# V2.net
KiCad netlist of a schematic drawn in EAGLE
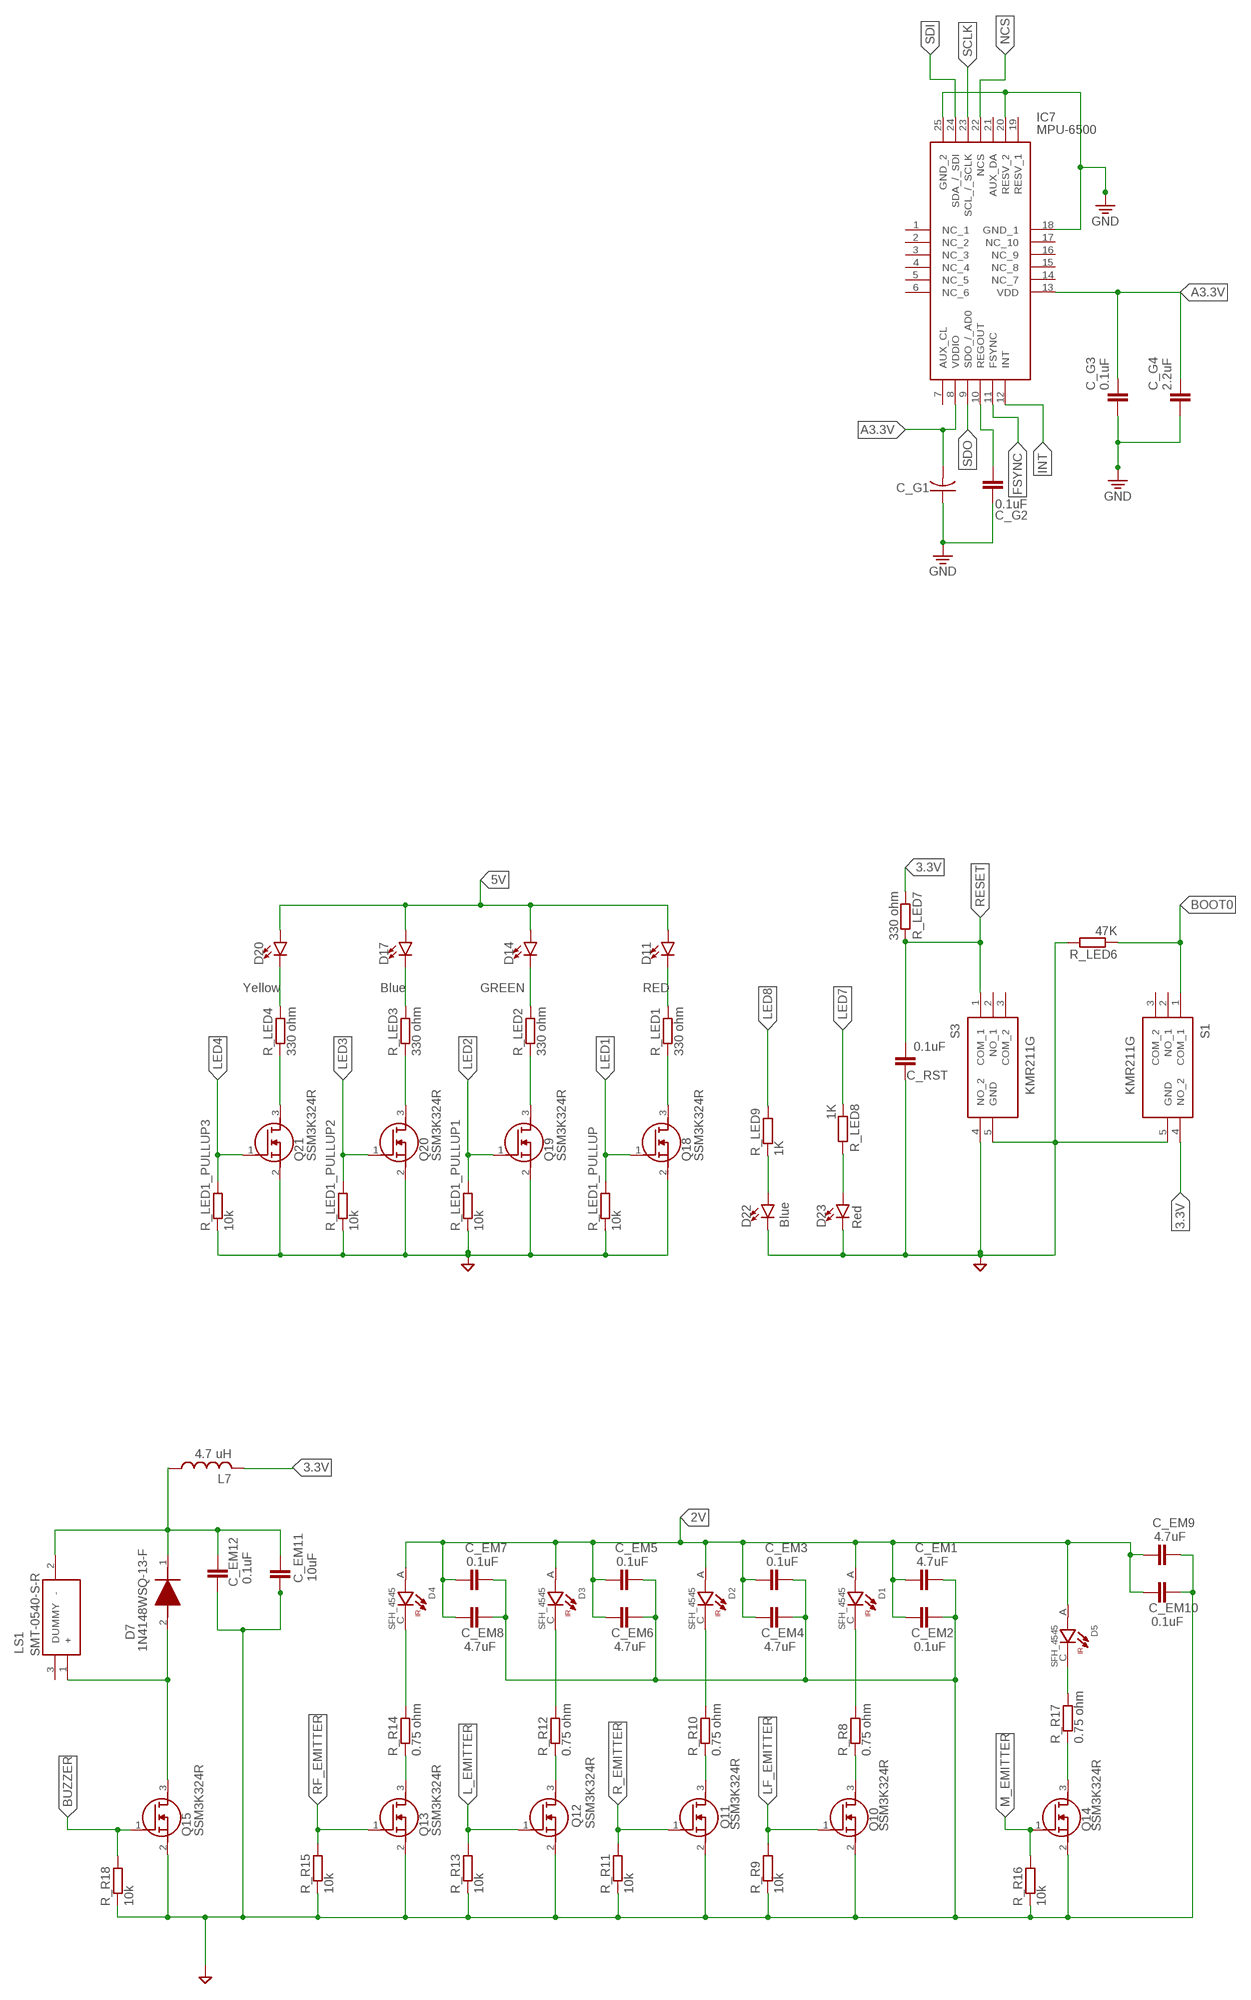
[diagram p0: schematic, sheet 1, part 1 of 2]
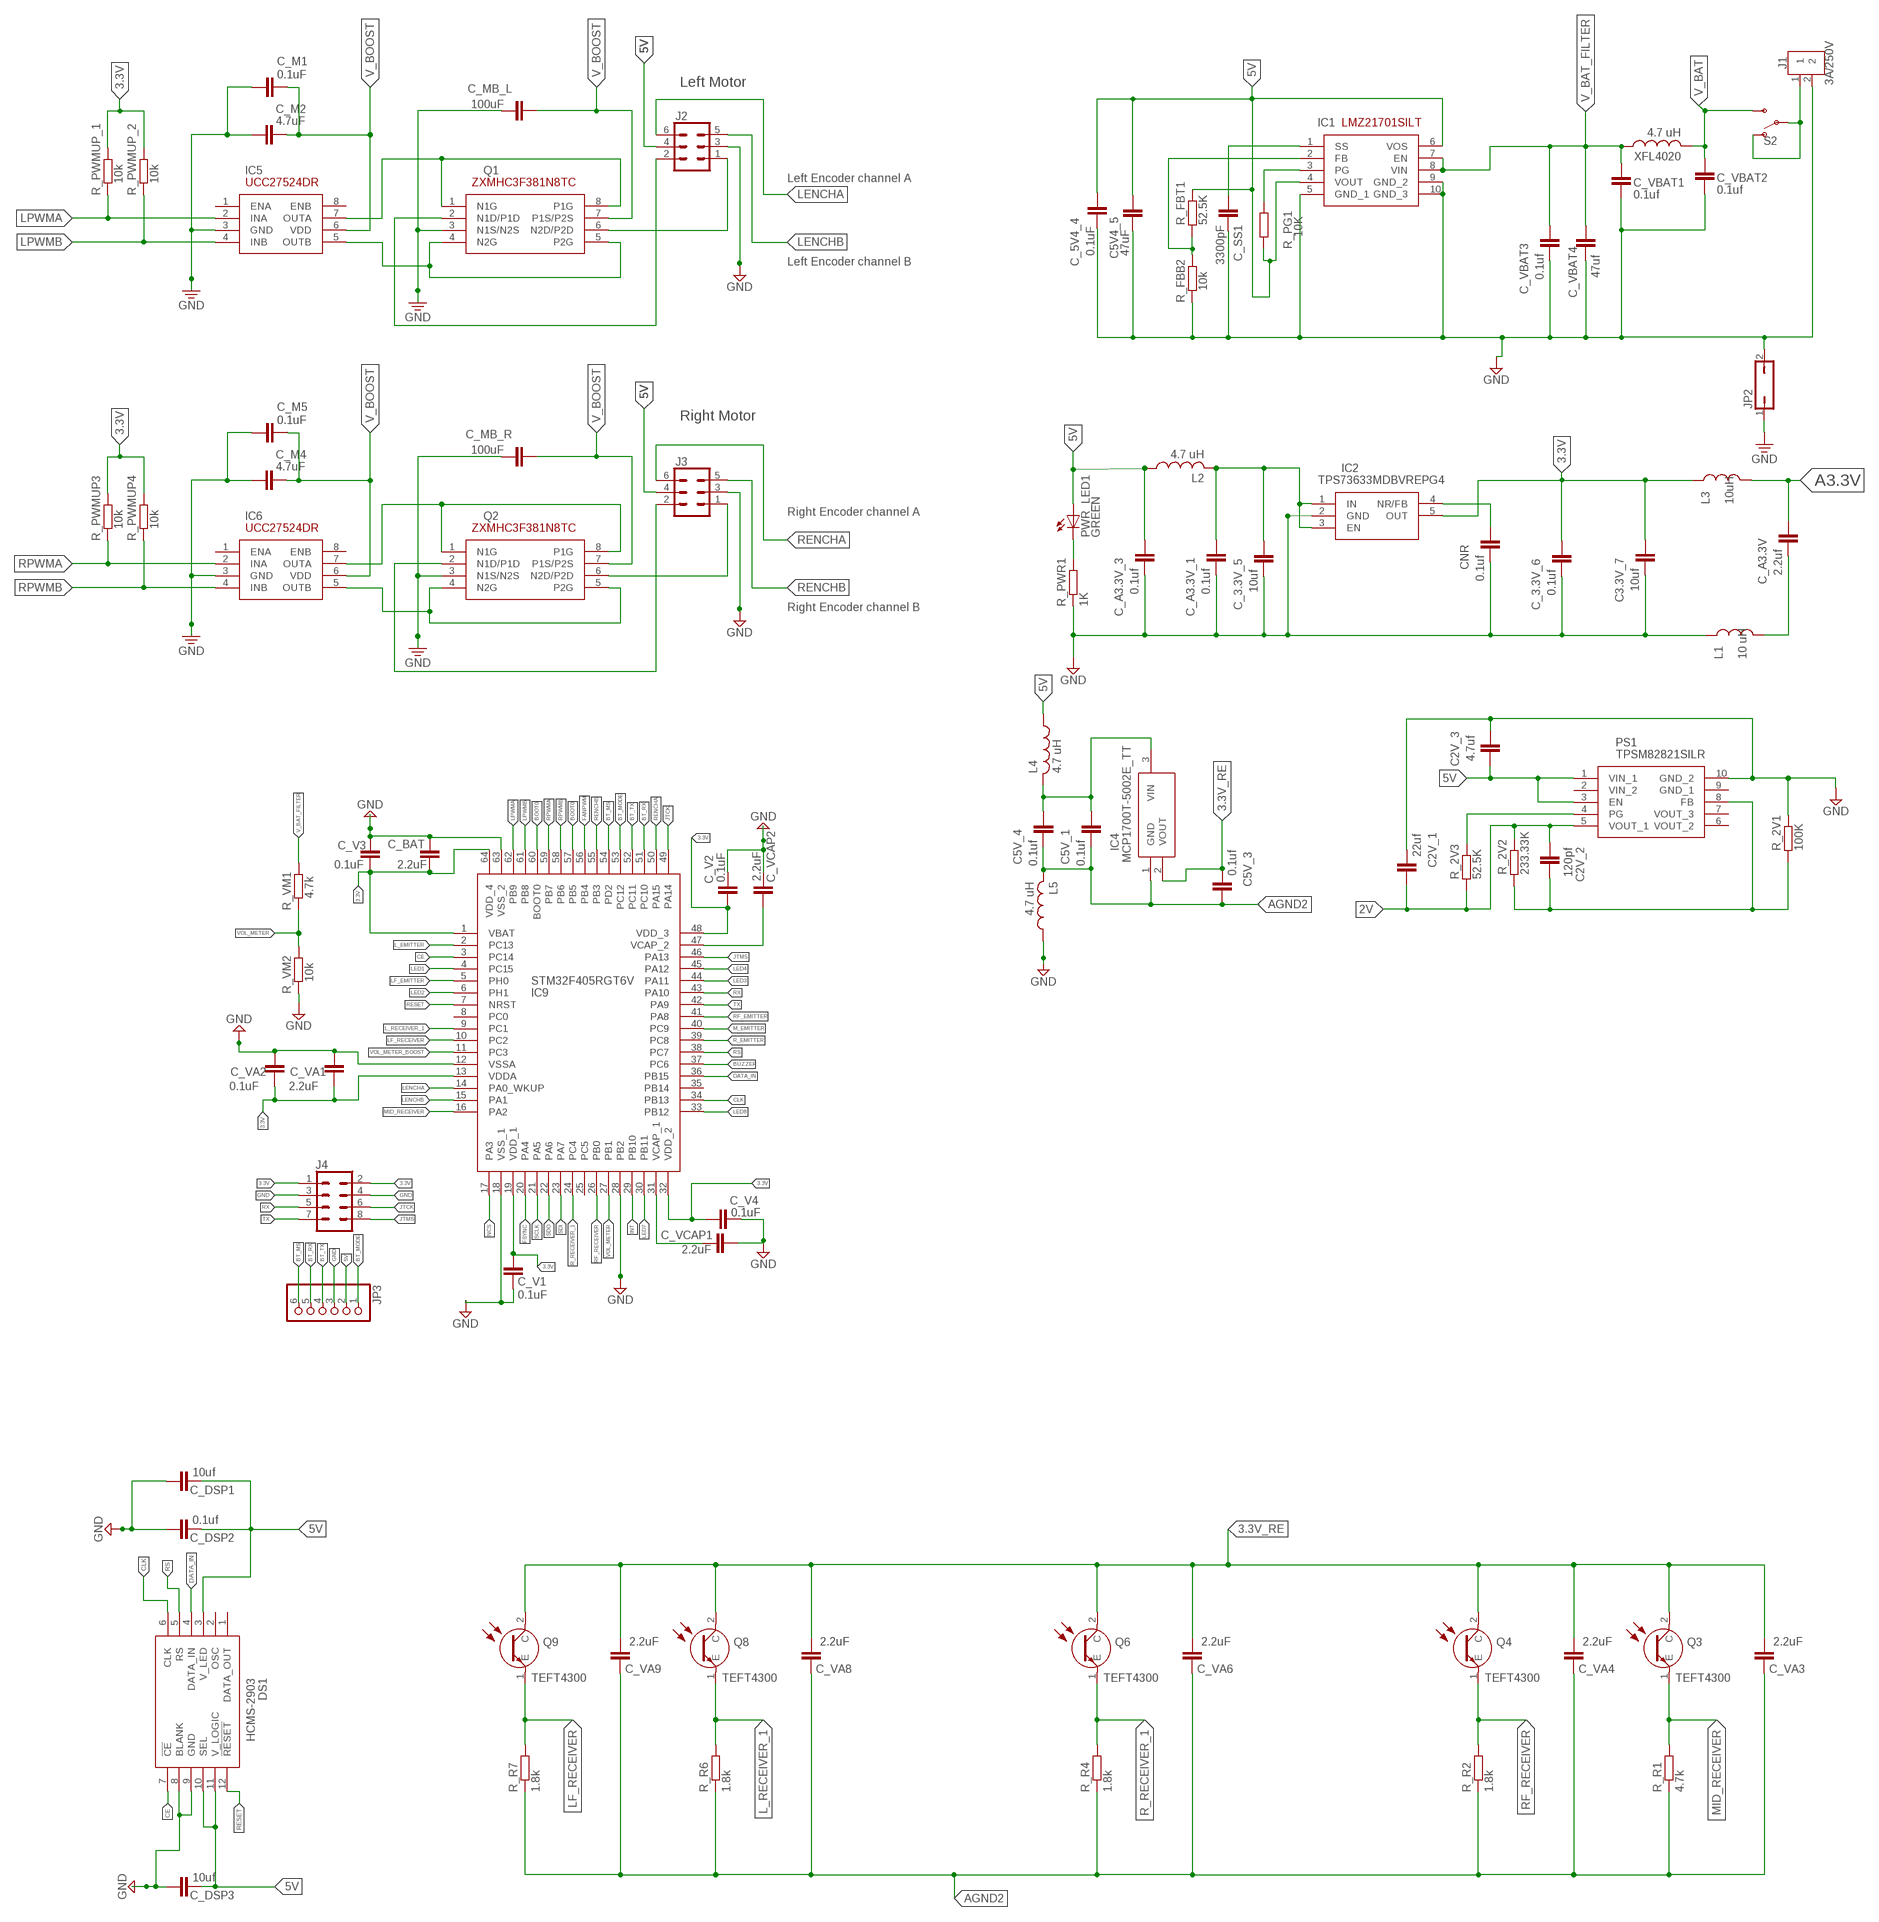
[diagram p1: schematic, sheet 1, part 2 of 2]

(export (version "E")
  (design (tool "Eeschema 10.0.6"))
  (components
    (comp (ref "C2V_1")
      (value "22uf")
      (footprint "eagle-import:CAPC2012X110")
      (libsource (lib "eagle-import") (part "CCHIP-0805(2012-METRIC)_"))
    )
    (comp (ref "C2V_2")
      (value "120pf")
      (footprint "eagle-import:CAPC2012X110")
      (libsource (lib "eagle-import") (part "CCHIP-0805(2012-METRIC)_"))
    )
    (comp (ref "C2V_3")
      (value "4.7uf")
      (footprint "eagle-import:CAPC2012X110")
      (libsource (lib "eagle-import") (part "CCHIP-0805(2012-METRIC)_"))
    )
    (comp (ref "C3.3V_7")
      (value "10uf")
      (footprint "eagle-import:CAPC2012X110")
      (libsource (lib "eagle-import") (part "CCHIP-0805(2012-METRIC)_"))
    )
    (comp (ref "C5V4_5")
      (value "47uF")
      (footprint "eagle-import:CAPC2012X110")
      (libsource (lib "eagle-import") (part "CCHIP-0805(2012-METRIC)_"))
    )
    (comp (ref "C5V_1")
      (value "0.1uf")
      (footprint "eagle-import:CAPC2012X110")
      (libsource (lib "eagle-import") (part "CCHIP-0805(2012-METRIC)_"))
    )
    (comp (ref "C5V_3")
      (value "0.1uf")
      (footprint "eagle-import:CAPC2012X110")
      (libsource (lib "eagle-import") (part "CCHIP-0805(2012-METRIC)_"))
    )
    (comp (ref "C5V_4")
      (value "0.1uf")
      (footprint "eagle-import:CAPC2012X110")
      (libsource (lib "eagle-import") (part "CCHIP-0805(2012-METRIC)_"))
    )
    (comp (ref "CNR")
      (value "0.1uf")
      (footprint "eagle-import:CAPC2012X110")
      (libsource (lib "eagle-import") (part "CCHIP-0805(2012-METRIC)_"))
    )
    (comp (ref "C_3.3V_5")
      (value "10uf")
      (footprint "eagle-import:CAPC2012X110")
      (libsource (lib "eagle-import") (part "CCHIP-0805(2012-METRIC)_"))
    )
    (comp (ref "C_3.3V_6")
      (value "0.1uf")
      (footprint "eagle-import:CAPC2012X110")
      (libsource (lib "eagle-import") (part "CCHIP-0805(2012-METRIC)_"))
    )
    (comp (ref "C_5V4_4")
      (value "0.1uF")
      (footprint "eagle-import:CAPC2012X110")
      (libsource (lib "eagle-import") (part "CCHIP-0805(2012-METRIC)_"))
    )
    (comp (ref "C_A3.3V")
      (value "2.2uf")
      (footprint "eagle-import:CAPC2012X110")
      (libsource (lib "eagle-import") (part "CCHIP-0805(2012-METRIC)_"))
    )
    (comp (ref "C_A3.3V_1")
      (value "0.1uf")
      (footprint "eagle-import:CAPC2012X110")
      (libsource (lib "eagle-import") (part "CCHIP-0805(2012-METRIC)_"))
    )
    (comp (ref "C_A3.3V_3")
      (value "0.1uf")
      (footprint "eagle-import:CAPC2012X110")
      (libsource (lib "eagle-import") (part "CCHIP-0805(2012-METRIC)_"))
    )
    (comp (ref "C_BAT")
      (value "2.2uF")
      (footprint "eagle-import:CAPC2012X110")
      (libsource (lib "eagle-import") (part "CCHIP-0805(2012-METRIC)_"))
    )
    (comp (ref "C_DSP1")
      (value "10uf")
      (footprint "eagle-import:CAPC2012X110")
      (libsource (lib "eagle-import") (part "CCHIP-0805(2012-METRIC)_"))
    )
    (comp (ref "C_DSP2")
      (value "0.1uf")
      (footprint "eagle-import:CAPC2012X110")
      (libsource (lib "eagle-import") (part "CCHIP-0805(2012-METRIC)_"))
    )
    (comp (ref "C_DSP3")
      (value "10uf")
      (footprint "eagle-import:CAPC2012X110")
      (libsource (lib "eagle-import") (part "CCHIP-0805(2012-METRIC)_"))
    )
    (comp (ref "C_EM1")
      (value "4.7uF")
      (footprint "eagle-import:CAPC2012X110")
      (libsource (lib "eagle-import") (part "CCHIP-0805(2012-METRIC)_"))
    )
    (comp (ref "C_EM2")
      (value "0.1uF")
      (footprint "eagle-import:CAPC2012X110")
      (libsource (lib "eagle-import") (part "CCHIP-0805(2012-METRIC)_"))
    )
    (comp (ref "C_EM3")
      (value "0.1uF")
      (footprint "eagle-import:CAPC2012X110")
      (libsource (lib "eagle-import") (part "CCHIP-0805(2012-METRIC)_"))
    )
    (comp (ref "C_EM4")
      (value "4.7uF")
      (footprint "eagle-import:CAPC2012X110")
      (libsource (lib "eagle-import") (part "CCHIP-0805(2012-METRIC)_"))
    )
    (comp (ref "C_EM5")
      (value "0.1uF")
      (footprint "eagle-import:CAPC2012X110")
      (libsource (lib "eagle-import") (part "CCHIP-0805(2012-METRIC)_"))
    )
    (comp (ref "C_EM6")
      (value "4.7uF")
      (footprint "eagle-import:CAPC2012X110")
      (libsource (lib "eagle-import") (part "CCHIP-0805(2012-METRIC)_"))
    )
    (comp (ref "C_EM7")
      (value "0.1uF")
      (footprint "eagle-import:CAPC2012X110")
      (libsource (lib "eagle-import") (part "CCHIP-0805(2012-METRIC)_"))
    )
    (comp (ref "C_EM8")
      (value "4.7uF")
      (footprint "eagle-import:CAPC2012X110")
      (libsource (lib "eagle-import") (part "CCHIP-0805(2012-METRIC)_"))
    )
    (comp (ref "C_EM9")
      (value "4.7uF")
      (footprint "eagle-import:CAPC2012X110")
      (libsource (lib "eagle-import") (part "CCHIP-0805(2012-METRIC)_"))
    )
    (comp (ref "C_EM10")
      (value "0.1uF")
      (footprint "eagle-import:CAPC2012X110")
      (libsource (lib "eagle-import") (part "CCHIP-0805(2012-METRIC)_"))
    )
    (comp (ref "C_EM11")
      (value "10uF")
      (footprint "eagle-import:CAPC2012X110")
      (libsource (lib "eagle-import") (part "CCHIP-0805(2012-METRIC)_"))
    )
    (comp (ref "C_EM12")
      (value "0.1uF")
      (footprint "eagle-import:CAPC2012X110")
      (libsource (lib "eagle-import") (part "CCHIP-0805(2012-METRIC)_"))
    )
    (comp (ref "C_G1")
      (value "0.01uF")
      (footprint "eagle-import:C0603K")
      (libsource (lib "eagle-import") (part "C-USC0603K"))
    )
    (comp (ref "C_G2")
      (value "0.1uF")
      (footprint "eagle-import:CAPC2012X110")
      (libsource (lib "eagle-import") (part "CCHIP-0805(2012-METRIC)_"))
    )
    (comp (ref "C_G3")
      (value "0.1uF")
      (footprint "eagle-import:CAPC2012X110")
      (libsource (lib "eagle-import") (part "CCHIP-0805(2012-METRIC)_"))
    )
    (comp (ref "C_G4")
      (value "2.2uF")
      (footprint "eagle-import:CAPC2012X110")
      (libsource (lib "eagle-import") (part "CCHIP-0805(2012-METRIC)_"))
    )
    (comp (ref "C_M1")
      (value "0.1uF")
      (footprint "eagle-import:CAPC2012X110")
      (libsource (lib "eagle-import") (part "CCHIP-0805(2012-METRIC)_"))
    )
    (comp (ref "C_M2")
      (value "4.7uF")
      (footprint "eagle-import:CAPC2012X110")
      (libsource (lib "eagle-import") (part "CCHIP-0805(2012-METRIC)_"))
    )
    (comp (ref "C_M4")
      (value "4.7uF")
      (footprint "eagle-import:CAPC2012X110")
      (libsource (lib "eagle-import") (part "CCHIP-0805(2012-METRIC)_"))
    )
    (comp (ref "C_M5")
      (value "0.1uF")
      (footprint "eagle-import:CAPC2012X110")
      (libsource (lib "eagle-import") (part "CCHIP-0805(2012-METRIC)_"))
    )
    (comp (ref "C_MB_L")
      (value "100uF")
      (footprint "eagle-import:CAPC2012X110")
      (libsource (lib "eagle-import") (part "CCHIP-0805(2012-METRIC)_"))
    )
    (comp (ref "C_MB_R")
      (value "100uF")
      (footprint "eagle-import:CAPC2012X110")
      (libsource (lib "eagle-import") (part "CCHIP-0805(2012-METRIC)_"))
    )
    (comp (ref "C_RST")
      (value "0.1uF")
      (footprint "eagle-import:CAPC2012X110")
      (libsource (lib "eagle-import") (part "CCHIP-0805(2012-METRIC)_"))
    )
    (comp (ref "C_SS1")
      (value "3300pF")
      (footprint "eagle-import:CAPC2012X110")
      (libsource (lib "eagle-import") (part "CCHIP-0805(2012-METRIC)_"))
    )
    (comp (ref "C_V1")
      (value "0.1uF")
      (footprint "eagle-import:CAPC2012X110")
      (libsource (lib "eagle-import") (part "CCHIP-0805(2012-METRIC)_"))
    )
    (comp (ref "C_V2")
      (value "0.1uF")
      (footprint "eagle-import:CAPC2012X110")
      (libsource (lib "eagle-import") (part "CCHIP-0805(2012-METRIC)_"))
    )
    (comp (ref "C_V3")
      (value "0.1uF")
      (footprint "eagle-import:CAPC2012X110")
      (libsource (lib "eagle-import") (part "CCHIP-0805(2012-METRIC)_"))
    )
    (comp (ref "C_V4")
      (value "0.1uF")
      (footprint "eagle-import:CAPC2012X110")
      (libsource (lib "eagle-import") (part "CCHIP-0805(2012-METRIC)_"))
    )
    (comp (ref "C_VA1")
      (value "2.2uF")
      (footprint "eagle-import:CAPC2012X110")
      (libsource (lib "eagle-import") (part "CCHIP-0805(2012-METRIC)_"))
    )
    (comp (ref "C_VA2")
      (value "0.1uF")
      (footprint "eagle-import:CAPC2012X110")
      (libsource (lib "eagle-import") (part "CCHIP-0805(2012-METRIC)_"))
    )
    (comp (ref "C_VA3")
      (value "2.2uF")
      (footprint "eagle-import:CAPC2012X110")
      (libsource (lib "eagle-import") (part "CCHIP-0805(2012-METRIC)_"))
    )
    (comp (ref "C_VA4")
      (value "2.2uF")
      (footprint "eagle-import:CAPC2012X110")
      (libsource (lib "eagle-import") (part "CCHIP-0805(2012-METRIC)_"))
    )
    (comp (ref "C_VA6")
      (value "2.2uF")
      (footprint "eagle-import:CAPC2012X110")
      (libsource (lib "eagle-import") (part "CCHIP-0805(2012-METRIC)_"))
    )
    (comp (ref "C_VA8")
      (value "2.2uF")
      (footprint "eagle-import:CAPC2012X110")
      (libsource (lib "eagle-import") (part "CCHIP-0805(2012-METRIC)_"))
    )
    (comp (ref "C_VA9")
      (value "2.2uF")
      (footprint "eagle-import:CAPC2012X110")
      (libsource (lib "eagle-import") (part "CCHIP-0805(2012-METRIC)_"))
    )
    (comp (ref "C_VBAT1")
      (value "0.1uf")
      (footprint "eagle-import:CAPC2012X110")
      (libsource (lib "eagle-import") (part "CCHIP-0805(2012-METRIC)_"))
    )
    (comp (ref "C_VBAT2")
      (value "0.1uf")
      (footprint "eagle-import:CAPC2012X110")
      (libsource (lib "eagle-import") (part "CCHIP-0805(2012-METRIC)_"))
    )
    (comp (ref "C_VBAT3")
      (value "0.1uf")
      (footprint "eagle-import:CAPC2012X110")
      (libsource (lib "eagle-import") (part "CCHIP-0805(2012-METRIC)_"))
    )
    (comp (ref "C_VBAT4")
      (value "47uf")
      (footprint "eagle-import:CAPC2012X110")
      (libsource (lib "eagle-import") (part "CCHIP-0805(2012-METRIC)_"))
    )
    (comp (ref "C_VCAP1")
      (value "2.2uF")
      (footprint "eagle-import:CAPC2012X110")
      (libsource (lib "eagle-import") (part "CCHIP-0805(2012-METRIC)_"))
    )
    (comp (ref "C_VCAP2")
      (value "2.2uF")
      (footprint "eagle-import:CAPC2012X110")
      (libsource (lib "eagle-import") (part "CCHIP-0805(2012-METRIC)_"))
    )
    (comp (ref "D1")
      (value "SFH_4545")
      (footprint "eagle-import:DIO_SFH_4545")
      (fields (field (name "MF") "OSRAM Opto") (field (name "MP") "SFH 4545"))
      (libsource (lib "eagle-import") (part "SFH_4545"))
    )
    (comp (ref "D2")
      (value "SFH_4545")
      (footprint "eagle-import:DIO_SFH_4545")
      (fields (field (name "MF") "OSRAM Opto") (field (name "MP") "SFH 4545"))
      (libsource (lib "eagle-import") (part "SFH_4545"))
    )
    (comp (ref "D3")
      (value "SFH_4545")
      (footprint "eagle-import:DIO_SFH_4545")
      (fields (field (name "MF") "OSRAM Opto") (field (name "MP") "SFH 4545"))
      (libsource (lib "eagle-import") (part "SFH_4545"))
    )
    (comp (ref "D4")
      (value "SFH_4545")
      (footprint "eagle-import:DIO_SFH_4545")
      (fields (field (name "MF") "OSRAM Opto") (field (name "MP") "SFH 4545"))
      (libsource (lib "eagle-import") (part "SFH_4545"))
    )
    (comp (ref "D5")
      (value "SFH_4545")
      (footprint "eagle-import:DIO_SFH_4545")
      (fields (field (name "MF") "OSRAM Opto") (field (name "MP") "SFH 4545"))
      (libsource (lib "eagle-import") (part "SFH_4545"))
    )
    (comp (ref "D7")
      (value "1N4148WSQ-13-F")
      (footprint "eagle-import:SOD2513X120N")
      (libsource (lib "eagle-import") (part "1N4148WSQ-13-F"))
    )
    (comp (ref "D11")
      (value "LED0603")
      (footprint "eagle-import:LED-0603")
      (libsource (lib "eagle-import") (part "LED0603"))
    )
    (comp (ref "D14")
      (value "LED0603")
      (footprint "eagle-import:LED-0603")
      (libsource (lib "eagle-import") (part "LED0603"))
    )
    (comp (ref "D17")
      (value "LED0603")
      (footprint "eagle-import:LED-0603")
      (libsource (lib "eagle-import") (part "LED0603"))
    )
    (comp (ref "D20")
      (value "LED0603")
      (footprint "eagle-import:LED-0603")
      (libsource (lib "eagle-import") (part "LED0603"))
    )
    (comp (ref "D22")
      (value "LED0603")
      (footprint "eagle-import:LED-0603")
      (libsource (lib "eagle-import") (part "LED0603"))
    )
    (comp (ref "D23")
      (value "LED0603")
      (footprint "eagle-import:LED-0603")
      (libsource (lib "eagle-import") (part "LED0603"))
    )
    (comp (ref "DS1")
      (value "HCMS-2903")
      (footprint "eagle-import:DIPS762W64P254L1778H508Q12N")
      (fields (field (name "MOUSER_PART_NUMBER") "630-HCMS-2903"))
      (libsource (lib "eagle-import") (part "HCMS-2903"))
    )
    (comp (ref "IC1")
      (value "LMZ21701SILT")
      (footprint "eagle-import:LMZ21701SILT")
      (fields (field (name "MOUSER_PART_NUMBER") "595-LMZ21701SILT") (field (name "SPICEPREFIX") "X"))
      (libsource (lib "eagle-import") (part "LMZ21701SILT"))
    )
    (comp (ref "IC2")
      (value "TPS73633MDBVREPG4")
      (footprint "eagle-import:SOT95P280X145-5N")
      (fields (field (name "MOUSER_PART_NUMBER") "595-PS73633MDBVREPG4") (field (name "SPICEPREFIX") "X"))
      (libsource (lib "eagle-import") (part "TPS73633MDBVREPG4"))
    )
    (comp (ref "IC4")
      (value "MCP1700T-5002E_TT")
      (footprint "eagle-import:SOT95P237X112-3N")
      (fields
        (field (name "ARROW_PART_NUMBER") "MCP1700T-5002E/TT")
        (field (name "MOUSER_PART_NUMBER") "579-MCP1700T5002E/TT")
        (field (name "SPICEPREFIX") "J")
      )
      (libsource (lib "eagle-import") (part "MCP1700T-5002E_TT"))
    )
    (comp (ref "IC5")
      (value "UCC27524DR")
      (footprint "eagle-import:SOIC127P600X175-8N")
      (fields (field (name "MOUSER_PART_NUMBER") "595-UCC27524DR"))
      (libsource (lib "eagle-import") (part "UCC27524DR"))
    )
    (comp (ref "IC6")
      (value "UCC27524DR")
      (footprint "eagle-import:SOIC127P600X175-8N")
      (fields (field (name "MOUSER_PART_NUMBER") "595-UCC27524DR"))
      (libsource (lib "eagle-import") (part "UCC27524DR"))
    )
    (comp (ref "IC7")
      (value "MPU-6500")
      (footprint "eagle-import:QFN40P300X300X95-25N")
      (fields (field (name "MOUSER_PART_NUMBER") "410-MPU-6500"))
      (libsource (lib "eagle-import") (part "MPU-6500"))
    )
    (comp (ref "IC9")
      (value "STM32F405RGT6V")
      (footprint "eagle-import:QFP50P1200X1200X160-64N")
      (fields (field (name "MOUSER_PART_NUMBER") "511-STM32F405RGT6V"))
      (libsource (lib "eagle-import") (part "STM32F405RGT6V"))
    )
    (comp (ref "J1")
      (value "3A/250V")
      (footprint "eagle-import:B2B-XH-A")
      (fields
        (field (name "MANUFACTURER") "JST (XH CONNECTOR)")
        (field (name "MPN") "B2B-XH-A")
        (field (name "SPICEPREFIX") "B")
      )
      (libsource (lib "eagle-import") (part "B2B-XH-A"))
    )
    (comp (ref "J2")
      (value "MA03-2")
      (footprint "eagle-import:MA03-2")
      (libsource (lib "eagle-import") (part "MA03-2"))
    )
    (comp (ref "J3")
      (value "MA03-2")
      (footprint "eagle-import:MA03-2")
      (libsource (lib "eagle-import") (part "MA03-2"))
    )
    (comp (ref "J4")
      (value "CONN_04X2")
      (footprint "eagle-import:2X4")
      (libsource (lib "eagle-import") (part "CONN_04X2"))
    )
    (comp (ref "JP2")
      (value "JP1Q")
      (footprint "eagle-import:JP1")
      (libsource (lib "eagle-import") (part "JP1Q"))
    )
    (comp (ref "JP3")
      (value "PINHD-1X6")
      (footprint "eagle-import:1X06")
      (libsource (lib "eagle-import") (part "PINHD-1X6"))
    )
    (comp (ref "L1")
      (value "10 uH")
      (footprint "eagle-import:INDC2009X120")
      (libsource (lib "eagle-import") (part "LCHIP-0805(2012-METRIC)_"))
    )
    (comp (ref "L2")
      (value "4.7 uH")
      (footprint "eagle-import:L4035M")
      (libsource (lib "eagle-import") (part "L-USL4035M"))
    )
    (comp (ref "L3")
      (value "10uH")
      (footprint "eagle-import:INDC2009X120")
      (libsource (lib "eagle-import") (part "LCHIP-0805(2012-METRIC)_"))
    )
    (comp (ref "L4")
      (value "4.7 uH")
      (footprint "eagle-import:L4035M")
      (libsource (lib "eagle-import") (part "L-USL4035M"))
    )
    (comp (ref "L5")
      (value "4.7 uH")
      (footprint "eagle-import:L4035M")
      (libsource (lib "eagle-import") (part "L-USL4035M"))
    )
    (comp (ref "L7")
      (value "4.7 uH")
      (footprint "eagle-import:L4035M")
      (libsource (lib "eagle-import") (part "L-USL4035M"))
    )
    (comp (ref "LS1")
      (value "SMT-0540-S-R")
      (footprint "eagle-import:SMT0540SR")
      (fields (field (name "MOUSER_PART_NUMBER") "665-SMT0540SR"))
      (libsource (lib "eagle-import") (part "SMT-0540-S-R"))
    )
    (comp (ref "PS1")
      (value "TPSM82821SILR")
      (footprint "eagle-import:TPSM82821SILR")
      (fields (field (name "MOUSER_PART_NUMBER") "595-TPSM82821SILR"))
      (libsource (lib "eagle-import") (part "TPSM82821SILR"))
    )
    (comp (ref "PWR_LED1")
      (value "GREEN")
      (footprint "eagle-import:CHIPLED_0603")
      (fields (field (name "SPICEPREFIX") "B"))
      (libsource (lib "eagle-import") (part "LEDCHIPLED_0603"))
    )
    (comp (ref "Q1")
      (value "ZXMHC3F381N8TC")
      (footprint "eagle-import:SOIC127P600X175-8N")
      (fields (field (name "MOUSER_PART_NUMBER") "522-ZXMHC3F381N8TC"))
      (libsource (lib "eagle-import") (part "ZXMHC3F381N8TC"))
    )
    (comp (ref "Q2")
      (value "ZXMHC3F381N8TC")
      (footprint "eagle-import:SOIC127P600X175-8N")
      (fields (field (name "MOUSER_PART_NUMBER") "522-ZXMHC3F381N8TC"))
      (libsource (lib "eagle-import") (part "ZXMHC3F381N8TC"))
    )
    (comp (ref "Q3")
      (value "TEFT4300")
      (footprint "eagle-import:TEFT4300")
      (fields (field (name "MOUSER_PART_NUMBER") "782-TEFT4300"))
      (libsource (lib "eagle-import") (part "TEFT4300"))
    )
    (comp (ref "Q4")
      (value "TEFT4300")
      (footprint "eagle-import:TEFT4300")
      (fields (field (name "MOUSER_PART_NUMBER") "782-TEFT4300"))
      (libsource (lib "eagle-import") (part "TEFT4300"))
    )
    (comp (ref "Q6")
      (value "TEFT4300")
      (footprint "eagle-import:TEFT4300")
      (fields (field (name "MOUSER_PART_NUMBER") "782-TEFT4300"))
      (libsource (lib "eagle-import") (part "TEFT4300"))
    )
    (comp (ref "Q8")
      (value "TEFT4300")
      (footprint "eagle-import:TEFT4300")
      (fields (field (name "MOUSER_PART_NUMBER") "782-TEFT4300"))
      (libsource (lib "eagle-import") (part "TEFT4300"))
    )
    (comp (ref "Q9")
      (value "TEFT4300")
      (footprint "eagle-import:TEFT4300")
      (fields (field (name "MOUSER_PART_NUMBER") "782-TEFT4300"))
      (libsource (lib "eagle-import") (part "TEFT4300"))
    )
    (comp (ref "Q10")
      (value "SSM3K324R")
      (footprint "eagle-import:SOT95P240X88-3N")
      (libsource (lib "eagle-import") (part "SSM3K324R"))
    )
    (comp (ref "Q11")
      (value "SSM3K324R")
      (footprint "eagle-import:SOT95P240X88-3N")
      (libsource (lib "eagle-import") (part "SSM3K324R"))
    )
    (comp (ref "Q12")
      (value "SSM3K324R")
      (footprint "eagle-import:SOT95P240X88-3N")
      (libsource (lib "eagle-import") (part "SSM3K324R"))
    )
    (comp (ref "Q13")
      (value "SSM3K324R")
      (footprint "eagle-import:SOT95P240X88-3N")
      (libsource (lib "eagle-import") (part "SSM3K324R"))
    )
    (comp (ref "Q14")
      (value "SSM3K324R")
      (footprint "eagle-import:SOT95P240X88-3N")
      (libsource (lib "eagle-import") (part "SSM3K324R"))
    )
    (comp (ref "Q15")
      (value "SSM3K324R")
      (footprint "eagle-import:SOT95P240X88-3N")
      (libsource (lib "eagle-import") (part "SSM3K324R"))
    )
    (comp (ref "Q18")
      (value "SSM3K324R")
      (footprint "eagle-import:SOT95P240X88-3N")
      (libsource (lib "eagle-import") (part "SSM3K324R"))
    )
    (comp (ref "Q19")
      (value "SSM3K324R")
      (footprint "eagle-import:SOT95P240X88-3N")
      (libsource (lib "eagle-import") (part "SSM3K324R"))
    )
    (comp (ref "Q20")
      (value "SSM3K324R")
      (footprint "eagle-import:SOT95P240X88-3N")
      (libsource (lib "eagle-import") (part "SSM3K324R"))
    )
    (comp (ref "Q21")
      (value "SSM3K324R")
      (footprint "eagle-import:SOT95P240X88-3N")
      (libsource (lib "eagle-import") (part "SSM3K324R"))
    )
    (comp (ref "R_2V1")
      (value "100K")
      (footprint "eagle-import:RESC1608X60")
      (fields (field (name "SPICEPREFIX") "R"))
      (libsource (lib "eagle-import") (part "RCHIP-0603(1608-METRIC)_"))
    )
    (comp (ref "R_2V2")
      (value "233.33K")
      (footprint "eagle-import:RESC1608X60")
      (fields (field (name "SPICEPREFIX") "R"))
      (libsource (lib "eagle-import") (part "RCHIP-0603(1608-METRIC)_"))
    )
    (comp (ref "R_2V3")
      (value "52.5K")
      (footprint "eagle-import:RESC1608X60")
      (fields (field (name "SPICEPREFIX") "R"))
      (libsource (lib "eagle-import") (part "RCHIP-0603(1608-METRIC)_"))
    )
    (comp (ref "R_FBB2")
      (value "10k")
      (footprint "eagle-import:RESC1608X60")
      (fields (field (name "SPICEPREFIX") "R"))
      (libsource (lib "eagle-import") (part "RCHIP-0603(1608-METRIC)_"))
    )
    (comp (ref "R_FBT1")
      (value "52.5K")
      (footprint "eagle-import:RESC1608X60")
      (fields (field (name "SPICEPREFIX") "R"))
      (libsource (lib "eagle-import") (part "RCHIP-0603(1608-METRIC)_"))
    )
    (comp (ref "R_LED1")
      (value "330 ohm")
      (footprint "eagle-import:RESC1608X60")
      (fields (field (name "SPICEPREFIX") "R"))
      (libsource (lib "eagle-import") (part "RCHIP-0603(1608-METRIC)_"))
    )
    (comp (ref "R_LED1_PULLUP")
      (value "10k")
      (footprint "eagle-import:RESC1608X60")
      (fields (field (name "SPICEPREFIX") "R"))
      (libsource (lib "eagle-import") (part "RCHIP-0603(1608-METRIC)_"))
    )
    (comp (ref "R_LED1_PULLUP1")
      (value "10k")
      (footprint "eagle-import:RESC1608X60")
      (fields (field (name "SPICEPREFIX") "R"))
      (libsource (lib "eagle-import") (part "RCHIP-0603(1608-METRIC)_"))
    )
    (comp (ref "R_LED1_PULLUP2")
      (value "10k")
      (footprint "eagle-import:RESC1608X60")
      (fields (field (name "SPICEPREFIX") "R"))
      (libsource (lib "eagle-import") (part "RCHIP-0603(1608-METRIC)_"))
    )
    (comp (ref "R_LED1_PULLUP3")
      (value "10k")
      (footprint "eagle-import:RESC1608X60")
      (fields (field (name "SPICEPREFIX") "R"))
      (libsource (lib "eagle-import") (part "RCHIP-0603(1608-METRIC)_"))
    )
    (comp (ref "R_LED2")
      (value "330 ohm")
      (footprint "eagle-import:RESC1608X60")
      (fields (field (name "SPICEPREFIX") "R"))
      (libsource (lib "eagle-import") (part "RCHIP-0603(1608-METRIC)_"))
    )
    (comp (ref "R_LED3")
      (value "330 ohm")
      (footprint "eagle-import:RESC1608X60")
      (fields (field (name "SPICEPREFIX") "R"))
      (libsource (lib "eagle-import") (part "RCHIP-0603(1608-METRIC)_"))
    )
    (comp (ref "R_LED4")
      (value "330 ohm")
      (footprint "eagle-import:RESC1608X60")
      (fields (field (name "SPICEPREFIX") "R"))
      (libsource (lib "eagle-import") (part "RCHIP-0603(1608-METRIC)_"))
    )
    (comp (ref "R_LED6")
      (value "47K")
      (footprint "eagle-import:RESC1608X60")
      (fields (field (name "SPICEPREFIX") "R"))
      (libsource (lib "eagle-import") (part "RCHIP-0603(1608-METRIC)_"))
    )
    (comp (ref "R_LED7")
      (value "330 ohm")
      (footprint "eagle-import:RESC1608X60")
      (fields (field (name "SPICEPREFIX") "R"))
      (libsource (lib "eagle-import") (part "RCHIP-0603(1608-METRIC)_"))
    )
    (comp (ref "R_LED8")
      (value "1K")
      (footprint "eagle-import:RESC1608X60")
      (fields (field (name "SPICEPREFIX") "R"))
      (libsource (lib "eagle-import") (part "RCHIP-0603(1608-METRIC)_"))
    )
    (comp (ref "R_LED9")
      (value "1K")
      (footprint "eagle-import:RESC1608X60")
      (fields (field (name "SPICEPREFIX") "R"))
      (libsource (lib "eagle-import") (part "RCHIP-0603(1608-METRIC)_"))
    )
    (comp (ref "R_PG1")
      (value "10K")
      (footprint "eagle-import:RESC1608X60")
      (fields (field (name "SPICEPREFIX") "R"))
      (libsource (lib "eagle-import") (part "RCHIP-0603(1608-METRIC)_"))
    )
    (comp (ref "R_PWMUP3")
      (value "10k")
      (footprint "eagle-import:RESC1608X60")
      (fields (field (name "SPICEPREFIX") "R"))
      (libsource (lib "eagle-import") (part "RCHIP-0603(1608-METRIC)_"))
    )
    (comp (ref "R_PWMUP4")
      (value "10k")
      (footprint "eagle-import:RESC1608X60")
      (fields (field (name "SPICEPREFIX") "R"))
      (libsource (lib "eagle-import") (part "RCHIP-0603(1608-METRIC)_"))
    )
    (comp (ref "R_PWMUP_1")
      (value "10k")
      (footprint "eagle-import:RESC1608X60")
      (fields (field (name "SPICEPREFIX") "R"))
      (libsource (lib "eagle-import") (part "RCHIP-0603(1608-METRIC)_"))
    )
    (comp (ref "R_PWMUP_2")
      (value "10k")
      (footprint "eagle-import:RESC1608X60")
      (fields (field (name "SPICEPREFIX") "R"))
      (libsource (lib "eagle-import") (part "RCHIP-0603(1608-METRIC)_"))
    )
    (comp (ref "R_PWR1")
      (value "1K")
      (footprint "eagle-import:RESC1608X60")
      (fields (field (name "SPICEPREFIX") "R"))
      (libsource (lib "eagle-import") (part "RCHIP-0603(1608-METRIC)_"))
    )
    (comp (ref "R_R1")
      (value "4.7k")
      (footprint "eagle-import:RESC1608X60")
      (fields (field (name "SPICEPREFIX") "R"))
      (libsource (lib "eagle-import") (part "RCHIP-0603(1608-METRIC)_"))
    )
    (comp (ref "R_R2")
      (value "1.8k")
      (footprint "eagle-import:RESC1608X60")
      (fields (field (name "SPICEPREFIX") "R"))
      (libsource (lib "eagle-import") (part "RCHIP-0603(1608-METRIC)_"))
    )
    (comp (ref "R_R4")
      (value "1.8k")
      (footprint "eagle-import:RESC1608X60")
      (fields (field (name "SPICEPREFIX") "R"))
      (libsource (lib "eagle-import") (part "RCHIP-0603(1608-METRIC)_"))
    )
    (comp (ref "R_R6")
      (value "1.8k")
      (footprint "eagle-import:RESC1608X60")
      (fields (field (name "SPICEPREFIX") "R"))
      (libsource (lib "eagle-import") (part "RCHIP-0603(1608-METRIC)_"))
    )
    (comp (ref "R_R7")
      (value "1.8k")
      (footprint "eagle-import:RESC1608X60")
      (fields (field (name "SPICEPREFIX") "R"))
      (libsource (lib "eagle-import") (part "RCHIP-0603(1608-METRIC)_"))
    )
    (comp (ref "R_R8")
      (value "0.75 ohm")
      (footprint "eagle-import:RESC1608X60")
      (fields (field (name "SPICEPREFIX") "R"))
      (libsource (lib "eagle-import") (part "RCHIP-0603(1608-METRIC)_"))
    )
    (comp (ref "R_R9")
      (value "10k")
      (footprint "eagle-import:RESC1608X60")
      (fields (field (name "SPICEPREFIX") "R"))
      (libsource (lib "eagle-import") (part "RCHIP-0603(1608-METRIC)_"))
    )
    (comp (ref "R_R10")
      (value "0.75 ohm")
      (footprint "eagle-import:RESC1608X60")
      (fields (field (name "SPICEPREFIX") "R"))
      (libsource (lib "eagle-import") (part "RCHIP-0603(1608-METRIC)_"))
    )
    (comp (ref "R_R11")
      (value "10k")
      (footprint "eagle-import:RESC1608X60")
      (fields (field (name "SPICEPREFIX") "R"))
      (libsource (lib "eagle-import") (part "RCHIP-0603(1608-METRIC)_"))
    )
    (comp (ref "R_R12")
      (value "0.75 ohm")
      (footprint "eagle-import:RESC1608X60")
      (fields (field (name "SPICEPREFIX") "R"))
      (libsource (lib "eagle-import") (part "RCHIP-0603(1608-METRIC)_"))
    )
    (comp (ref "R_R13")
      (value "10k")
      (footprint "eagle-import:RESC1608X60")
      (fields (field (name "SPICEPREFIX") "R"))
      (libsource (lib "eagle-import") (part "RCHIP-0603(1608-METRIC)_"))
    )
    (comp (ref "R_R14")
      (value "0.75 ohm")
      (footprint "eagle-import:RESC1608X60")
      (fields (field (name "SPICEPREFIX") "R"))
      (libsource (lib "eagle-import") (part "RCHIP-0603(1608-METRIC)_"))
    )
    (comp (ref "R_R15")
      (value "10k")
      (footprint "eagle-import:RESC1608X60")
      (fields (field (name "SPICEPREFIX") "R"))
      (libsource (lib "eagle-import") (part "RCHIP-0603(1608-METRIC)_"))
    )
    (comp (ref "R_R16")
      (value "10k")
      (footprint "eagle-import:RESC1608X60")
      (fields (field (name "SPICEPREFIX") "R"))
      (libsource (lib "eagle-import") (part "RCHIP-0603(1608-METRIC)_"))
    )
    (comp (ref "R_R17")
      (value "0.75 ohm")
      (footprint "eagle-import:RESC1608X60")
      (fields (field (name "SPICEPREFIX") "R"))
      (libsource (lib "eagle-import") (part "RCHIP-0603(1608-METRIC)_"))
    )
    (comp (ref "R_R18")
      (value "10k")
      (footprint "eagle-import:RESC1608X60")
      (fields (field (name "SPICEPREFIX") "R"))
      (libsource (lib "eagle-import") (part "RCHIP-0603(1608-METRIC)_"))
    )
    (comp (ref "R_VM1")
      (value "4.7k")
      (footprint "eagle-import:RESC1608X60")
      (fields (field (name "SPICEPREFIX") "R"))
      (libsource (lib "eagle-import") (part "RCHIP-0603(1608-METRIC)_"))
    )
    (comp (ref "R_VM2")
      (value "10k")
      (footprint "eagle-import:RESC1608X60")
      (fields (field (name "SPICEPREFIX") "R"))
      (libsource (lib "eagle-import") (part "RCHIP-0603(1608-METRIC)_"))
    )
    (comp (ref "S1")
      (value "KMR211G")
      (footprint "eagle-import:KMR211G")
      (libsource (lib "eagle-import") (part "KMR211G"))
    )
    (comp (ref "S2")
      (value "SWITCH-SPDT-PTH-11.6X4.0MM")
      (footprint "eagle-import:SWITCH_SPDT_PTH_11.6X4.0MM")
      (libsource (lib "eagle-import") (part "SWITCH-SPDT-PTH-11.6X4.0MM"))
    )
    (comp (ref "S3")
      (value "KMR211G")
      (footprint "eagle-import:KMR211G")
      (libsource (lib "eagle-import") (part "KMR211G"))
    )
    (comp (ref "XFL4020")
      (value "4.7 uH")
      (footprint "eagle-import:L4035M")
      (libsource (lib "eagle-import") (part "L-USL4035M"))
    )
  )
  (nets
    (net (code "1") (name "2V") (class "Default")
      (node (ref "C2V_1") (pin "2") (pinfunction "2_2") (pintype "passive"))
      (node (ref "C2V_2") (pin "1") (pinfunction "1_1") (pintype "passive"))
      (node (ref "C_EM1") (pin "1") (pinfunction "1_1") (pintype "passive"))
      (node (ref "C_EM10") (pin "1") (pinfunction "1_1") (pintype "passive"))
      (node (ref "C_EM2") (pin "1") (pinfunction "1_1") (pintype "passive"))
      (node (ref "C_EM3") (pin "1") (pinfunction "1_1") (pintype "passive"))
      (node (ref "C_EM4") (pin "1") (pinfunction "1_1") (pintype "passive"))
      (node (ref "C_EM5") (pin "1") (pinfunction "1_1") (pintype "passive"))
      (node (ref "C_EM6") (pin "1") (pinfunction "1_1") (pintype "passive"))
      (node (ref "C_EM7") (pin "1") (pinfunction "1_1") (pintype "passive"))
      (node (ref "C_EM8") (pin "1") (pinfunction "1_1") (pintype "passive"))
      (node (ref "C_EM9") (pin "1") (pinfunction "1_1") (pintype "passive"))
      (node (ref "D1") (pin "A") (pinfunction "A_A") (pintype "passive"))
      (node (ref "D2") (pin "A") (pinfunction "A_A") (pintype "passive"))
      (node (ref "D3") (pin "A") (pinfunction "A_A") (pintype "passive"))
      (node (ref "D4") (pin "A") (pinfunction "A_A") (pintype "passive"))
      (node (ref "D5") (pin "A") (pinfunction "A_A") (pintype "passive"))
      (node (ref "PS1") (pin "5") (pinfunction "VOUT_1_5") (pintype "bidirectional"))
      (node (ref "R_2V2") (pin "2") (pinfunction "2_2") (pintype "passive"))
      (node (ref "R_2V3") (pin "1") (pinfunction "1_1") (pintype "passive"))
    )
    (net (code "2") (name "3.3V") (class "Default")
      (node (ref "C3.3V_7") (pin "2") (pinfunction "2_2") (pintype "passive"))
      (node (ref "C_3.3V_6") (pin "2") (pinfunction "2_2") (pintype "passive"))
      (node (ref "C_BAT") (pin "1") (pinfunction "1_1") (pintype "passive"))
      (node (ref "C_V1") (pin "2") (pinfunction "2_2") (pintype "passive"))
      (node (ref "C_V2") (pin "1") (pinfunction "1_1") (pintype "passive"))
      (node (ref "C_V3") (pin "1") (pinfunction "1_1") (pintype "passive"))
      (node (ref "C_V4") (pin "1") (pinfunction "1_1") (pintype "passive"))
      (node (ref "C_VA1") (pin "1") (pinfunction "1_1") (pintype "passive"))
      (node (ref "C_VA2") (pin "1") (pinfunction "1_1") (pintype "passive"))
      (node (ref "IC2") (pin "5") (pinfunction "OUT_5") (pintype "bidirectional"))
      (node (ref "IC9") (pin "1") (pinfunction "VBAT_1") (pintype "bidirectional"))
      (node (ref "IC9") (pin "13") (pinfunction "VDDA_13") (pintype "power_in"))
      (node (ref "IC9") (pin "19") (pinfunction "VDD_1_19") (pintype "power_in"))
      (node (ref "IC9") (pin "32") (pinfunction "VDD_2_32") (pintype "power_in"))
      (node (ref "IC9") (pin "48") (pinfunction "VDD_3_48") (pintype "power_in"))
      (node (ref "IC9") (pin "64") (pinfunction "VDD_4_64") (pintype "power_in"))
      (node (ref "J4") (pin "1") (pinfunction "1_1") (pintype "passive"))
      (node (ref "J4") (pin "2") (pinfunction "2_2") (pintype "passive"))
      (node (ref "L3") (pin "1") (pinfunction "1_1") (pintype "passive"))
      (node (ref "L7") (pin "2") (pinfunction "2_2") (pintype "passive"))
      (node (ref "R_LED7") (pin "1") (pinfunction "1_1") (pintype "passive"))
      (node (ref "R_PWMUP3") (pin "2") (pinfunction "2_2") (pintype "passive"))
      (node (ref "R_PWMUP4") (pin "2") (pinfunction "2_2") (pintype "passive"))
      (node (ref "R_PWMUP_1") (pin "2") (pinfunction "2_2") (pintype "passive"))
      (node (ref "R_PWMUP_2") (pin "2") (pinfunction "2_2") (pintype "passive"))
      (node (ref "S1") (pin "4") (pinfunction "NO_2_4") (pintype "bidirectional"))
    )
    (net (code "3") (name "3.3V_RE") (class "Default")
      (node (ref "C5V_3") (pin "1") (pinfunction "1_1") (pintype "passive"))
      (node (ref "C_VA3") (pin "1") (pinfunction "1_1") (pintype "passive"))
      (node (ref "C_VA4") (pin "1") (pinfunction "1_1") (pintype "passive"))
      (node (ref "C_VA6") (pin "1") (pinfunction "1_1") (pintype "passive"))
      (node (ref "C_VA8") (pin "1") (pinfunction "1_1") (pintype "passive"))
      (node (ref "C_VA9") (pin "1") (pinfunction "1_1") (pintype "passive"))
      (node (ref "IC4") (pin "2") (pinfunction "VOUT_2") (pintype "bidirectional"))
      (node (ref "Q3") (pin "2") (pinfunction "C_2") (pintype "bidirectional"))
      (node (ref "Q4") (pin "2") (pinfunction "C_2") (pintype "bidirectional"))
      (node (ref "Q6") (pin "2") (pinfunction "C_2") (pintype "bidirectional"))
      (node (ref "Q8") (pin "2") (pinfunction "C_2") (pintype "bidirectional"))
      (node (ref "Q9") (pin "2") (pinfunction "C_2") (pintype "bidirectional"))
    )
    (net (code "4") (name "5V") (class "Default")
      (node (ref "C2V_3") (pin "2") (pinfunction "2_2") (pintype "passive"))
      (node (ref "C5V4_5") (pin "1") (pinfunction "1_1") (pintype "passive"))
      (node (ref "C_5V4_4") (pin "2") (pinfunction "2_2") (pintype "passive"))
      (node (ref "C_A3.3V_3") (pin "2") (pinfunction "2_2") (pintype "passive"))
      (node (ref "C_DSP1") (pin "1") (pinfunction "1_1") (pintype "passive"))
      (node (ref "C_DSP2") (pin "1") (pinfunction "1_1") (pintype "passive"))
      (node (ref "C_DSP3") (pin "1") (pinfunction "1_1") (pintype "passive"))
      (node (ref "D11") (pin "A") (pinfunction "A_A") (pintype "passive"))
      (node (ref "D14") (pin "A") (pinfunction "A_A") (pintype "passive"))
      (node (ref "D17") (pin "A") (pinfunction "A_A") (pintype "passive"))
      (node (ref "D20") (pin "A") (pinfunction "A_A") (pintype "passive"))
      (node (ref "DS1") (pin "10") (pinfunction "SEL_10") (pintype "bidirectional"))
      (node (ref "DS1") (pin "11") (pinfunction "V_LOGIC_11") (pintype "bidirectional"))
      (node (ref "DS1") (pin "3") (pinfunction "V_LED_3") (pintype "bidirectional"))
      (node (ref "IC1") (pin "4") (pinfunction "VOUT_4") (pintype "output"))
      (node (ref "IC1") (pin "6") (pinfunction "VOS_6") (pintype "bidirectional"))
      (node (ref "J2") (pin "4") (pinfunction "4_4") (pintype "passive"))
      (node (ref "J3") (pin "4") (pinfunction "4_4") (pintype "passive"))
      (node (ref "JP3") (pin "2") (pinfunction "2_2") (pintype "passive"))
      (node (ref "L2") (pin "1") (pinfunction "1_1") (pintype "passive"))
      (node (ref "L4") (pin "1") (pinfunction "1_1") (pintype "passive"))
      (node (ref "PS1") (pin "1") (pinfunction "VIN_1_1") (pintype "bidirectional"))
      (node (ref "PS1") (pin "3") (pinfunction "EN_3") (pintype "bidirectional"))
      (node (ref "PWR_LED1") (pin "A") (pinfunction "A_A") (pintype "passive"))
      (node (ref "R_FBT1") (pin "2") (pinfunction "2_2") (pintype "passive"))
      (node (ref "R_PG1") (pin "1") (pinfunction "1_1") (pintype "passive"))
    )
    (net (code "5") (name "A3.3V") (class "Default")
      (node (ref "C_A3.3V") (pin "2") (pinfunction "2_2") (pintype "passive"))
      (node (ref "C_G1") (pin "2") (pinfunction "2_2") (pintype "passive"))
      (node (ref "C_G3") (pin "1") (pinfunction "1_1") (pintype "passive"))
      (node (ref "C_G4") (pin "1") (pinfunction "1_1") (pintype "passive"))
      (node (ref "IC7") (pin "13") (pinfunction "VDD_13") (pintype "bidirectional"))
      (node (ref "IC7") (pin "8") (pinfunction "VDDIO_8") (pintype "bidirectional"))
      (node (ref "L3") (pin "2") (pinfunction "2_2") (pintype "passive"))
    )
    (net (code "6") (name "AGND2") (class "Default")
      (node (ref "C5V_1") (pin "1") (pinfunction "1_1") (pintype "passive"))
      (node (ref "C5V_3") (pin "2") (pinfunction "2_2") (pintype "passive"))
      (node (ref "C5V_4") (pin "1") (pinfunction "1_1") (pintype "passive"))
      (node (ref "C_VA3") (pin "2") (pinfunction "2_2") (pintype "passive"))
      (node (ref "C_VA4") (pin "2") (pinfunction "2_2") (pintype "passive"))
      (node (ref "C_VA6") (pin "2") (pinfunction "2_2") (pintype "passive"))
      (node (ref "C_VA8") (pin "2") (pinfunction "2_2") (pintype "passive"))
      (node (ref "C_VA9") (pin "2") (pinfunction "2_2") (pintype "passive"))
      (node (ref "IC4") (pin "1") (pinfunction "GND_1") (pintype "bidirectional"))
      (node (ref "L5") (pin "2") (pinfunction "2_2") (pintype "passive"))
      (node (ref "R_R1") (pin "1") (pinfunction "1_1") (pintype "passive"))
      (node (ref "R_R2") (pin "1") (pinfunction "1_1") (pintype "passive"))
      (node (ref "R_R4") (pin "1") (pinfunction "1_1") (pintype "passive"))
      (node (ref "R_R6") (pin "1") (pinfunction "1_1") (pintype "passive"))
      (node (ref "R_R7") (pin "1") (pinfunction "1_1") (pintype "passive"))
    )
    (net (code "7") (name "BOOT0") (class "Default")
      (node (ref "IC9") (pin "57") (pinfunction "PB5_57") (pintype "bidirectional"))
      (node (ref "IC9") (pin "60") (pinfunction "BOOT0_60") (pintype "bidirectional"))
      (node (ref "R_LED6") (pin "1") (pinfunction "1_1") (pintype "passive"))
      (node (ref "S1") (pin "1") (pinfunction "COM_1_1") (pintype "bidirectional"))
    )
    (net (code "8") (name "BT_MODE") (class "Default")
      (node (ref "IC9") (pin "53") (pinfunction "PC12_53") (pintype "bidirectional"))
      (node (ref "JP3") (pin "1") (pinfunction "1_1") (pintype "passive"))
    )
    (net (code "9") (name "BT_MS") (class "Default")
      (node (ref "IC9") (pin "54") (pinfunction "PD2_54") (pintype "bidirectional"))
      (node (ref "JP3") (pin "6") (pinfunction "6_6") (pintype "passive"))
    )
    (net (code "10") (name "BT_RX") (class "Default")
      (node (ref "IC9") (pin "51") (pinfunction "PC10_51") (pintype "bidirectional"))
      (node (ref "JP3") (pin "5") (pinfunction "5_5") (pintype "passive"))
    )
    (net (code "11") (name "BT_TX") (class "Default")
      (node (ref "IC9") (pin "52") (pinfunction "PC11_52") (pintype "bidirectional"))
      (node (ref "JP3") (pin "4") (pinfunction "4_4") (pintype "passive"))
    )
    (net (code "12") (name "BUZZER") (class "Default")
      (node (ref "IC9") (pin "37") (pinfunction "PC6_37") (pintype "bidirectional"))
      (node (ref "Q15") (pin "1") (pinfunction "G_1") (pintype "input"))
      (node (ref "R_R18") (pin "2") (pinfunction "2_2") (pintype "passive"))
    )
    (net (code "13") (name "CE") (class "Default")
      (node (ref "DS1") (pin "7") (pinfunction "~{CE}_7") (pintype "bidirectional"))
      (node (ref "IC9") (pin "3") (pinfunction "PC14_3") (pintype "bidirectional"))
    )
    (net (code "14") (name "CLK") (class "Default")
      (node (ref "DS1") (pin "6") (pinfunction "CLK_6") (pintype "bidirectional"))
      (node (ref "IC9") (pin "34") (pinfunction "PB13_34") (pintype "bidirectional"))
    )
    (net (code "15") (name "DATA_IN") (class "Default")
      (node (ref "DS1") (pin "4") (pinfunction "DATA_IN_4") (pintype "bidirectional"))
      (node (ref "IC9") (pin "36") (pinfunction "PB15_36") (pintype "bidirectional"))
    )
    (net (code "16") (name "FANPWM") (class "Default")
      (node (ref "IC9") (pin "56") (pinfunction "PB4_56") (pintype "bidirectional"))
    )
    (net (code "17") (name "FSYNC") (class "Default")
      (node (ref "IC7") (pin "11") (pinfunction "FSYNC_11") (pintype "bidirectional"))
      (node (ref "IC9") (pin "20") (pinfunction "PA4_20") (pintype "bidirectional"))
    )
    (net (code "18") (name "GND") (class "Default")
      (node (ref "C2V_1") (pin "1") (pinfunction "1_1") (pintype "passive"))
      (node (ref "C2V_3") (pin "1") (pinfunction "1_1") (pintype "passive"))
      (node (ref "C3.3V_7") (pin "1") (pinfunction "1_1") (pintype "passive"))
      (node (ref "C5V4_5") (pin "2") (pinfunction "2_2") (pintype "passive"))
      (node (ref "CNR") (pin "1") (pinfunction "1_1") (pintype "passive"))
      (node (ref "C_3.3V_5") (pin "1") (pinfunction "1_1") (pintype "passive"))
      (node (ref "C_3.3V_6") (pin "1") (pinfunction "1_1") (pintype "passive"))
      (node (ref "C_5V4_4") (pin "1") (pinfunction "1_1") (pintype "passive"))
      (node (ref "C_A3.3V_1") (pin "1") (pinfunction "1_1") (pintype "passive"))
      (node (ref "C_A3.3V_3") (pin "1") (pinfunction "1_1") (pintype "passive"))
      (node (ref "C_BAT") (pin "2") (pinfunction "2_2") (pintype "passive"))
      (node (ref "C_DSP1") (pin "2") (pinfunction "2_2") (pintype "passive"))
      (node (ref "C_DSP2") (pin "2") (pinfunction "2_2") (pintype "passive"))
      (node (ref "C_DSP3") (pin "2") (pinfunction "2_2") (pintype "passive"))
      (node (ref "C_EM1") (pin "2") (pinfunction "2_2") (pintype "passive"))
      (node (ref "C_EM10") (pin "2") (pinfunction "2_2") (pintype "passive"))
      (node (ref "C_EM11") (pin "2") (pinfunction "2_2") (pintype "passive"))
      (node (ref "C_EM12") (pin "1") (pinfunction "1_1") (pintype "passive"))
      (node (ref "C_EM2") (pin "2") (pinfunction "2_2") (pintype "passive"))
      (node (ref "C_EM3") (pin "2") (pinfunction "2_2") (pintype "passive"))
      (node (ref "C_EM4") (pin "2") (pinfunction "2_2") (pintype "passive"))
      (node (ref "C_EM5") (pin "2") (pinfunction "2_2") (pintype "passive"))
      (node (ref "C_EM6") (pin "2") (pinfunction "2_2") (pintype "passive"))
      (node (ref "C_EM7") (pin "2") (pinfunction "2_2") (pintype "passive"))
      (node (ref "C_EM8") (pin "2") (pinfunction "2_2") (pintype "passive"))
      (node (ref "C_EM9") (pin "2") (pinfunction "2_2") (pintype "passive"))
      (node (ref "C_M1") (pin "2") (pinfunction "2_2") (pintype "passive"))
      (node (ref "C_M2") (pin "1") (pinfunction "1_1") (pintype "passive"))
      (node (ref "C_M4") (pin "1") (pinfunction "1_1") (pintype "passive"))
      (node (ref "C_M5") (pin "2") (pinfunction "2_2") (pintype "passive"))
      (node (ref "C_MB_L") (pin "1") (pinfunction "1_1") (pintype "passive"))
      (node (ref "C_MB_R") (pin "1") (pinfunction "1_1") (pintype "passive"))
      (node (ref "C_RST") (pin "2") (pinfunction "2_2") (pintype "passive"))
      (node (ref "C_SS1") (pin "1") (pinfunction "1_1") (pintype "passive"))
      (node (ref "C_V1") (pin "1") (pinfunction "1_1") (pintype "passive"))
      (node (ref "C_V2") (pin "2") (pinfunction "2_2") (pintype "passive"))
      (node (ref "C_V3") (pin "2") (pinfunction "2_2") (pintype "passive"))
      (node (ref "C_V4") (pin "2") (pinfunction "2_2") (pintype "passive"))
      (node (ref "C_VA1") (pin "2") (pinfunction "2_2") (pintype "passive"))
      (node (ref "C_VA2") (pin "2") (pinfunction "2_2") (pintype "passive"))
      (node (ref "C_VBAT1") (pin "2") (pinfunction "2_2") (pintype "passive"))
      (node (ref "C_VBAT2") (pin "2") (pinfunction "2_2") (pintype "passive"))
      (node (ref "C_VBAT3") (pin "1") (pinfunction "1_1") (pintype "passive"))
      (node (ref "C_VBAT4") (pin "1") (pinfunction "1_1") (pintype "passive"))
      (node (ref "C_VCAP1") (pin "1") (pinfunction "1_1") (pintype "passive"))
      (node (ref "C_VCAP2") (pin "2") (pinfunction "2_2") (pintype "passive"))
      (node (ref "D22") (pin "C") (pinfunction "C_C") (pintype "passive"))
      (node (ref "D23") (pin "C") (pinfunction "C_C") (pintype "passive"))
      (node (ref "DS1") (pin "8") (pinfunction "BLANK_8") (pintype "bidirectional"))
      (node (ref "DS1") (pin "9") (pinfunction "GND_9") (pintype "bidirectional"))
      (node (ref "IC1") (pin "10") (pinfunction "GND_3_10") (pintype "power_in"))
      (node (ref "IC1") (pin "5") (pinfunction "GND_1_5") (pintype "power_in"))
      (node (ref "IC1") (pin "9") (pinfunction "GND_2_9") (pintype "power_in"))
      (node (ref "IC2") (pin "2") (pinfunction "GND_2") (pintype "bidirectional"))
      (node (ref "IC5") (pin "3") (pinfunction "GND_3") (pintype "power_in"))
      (node (ref "IC6") (pin "3") (pinfunction "GND_3") (pintype "power_in"))
      (node (ref "IC9") (pin "12") (pinfunction "VSSA_12") (pintype "power_in"))
      (node (ref "IC9") (pin "18") (pinfunction "VSS_1_18") (pintype "power_in"))
      (node (ref "IC9") (pin "28") (pinfunction "PB2_28") (pintype "bidirectional"))
      (node (ref "IC9") (pin "63") (pinfunction "VSS_2_63") (pintype "power_in"))
      (node (ref "J1") (pin "2") (pinfunction "2_2") (pintype "bidirectional"))
      (node (ref "J2") (pin "3") (pinfunction "3_3") (pintype "passive"))
      (node (ref "J3") (pin "3") (pinfunction "3_3") (pintype "passive"))
      (node (ref "J4") (pin "3") (pinfunction "3_3") (pintype "passive"))
      (node (ref "J4") (pin "4") (pinfunction "4_4") (pintype "passive"))
      (node (ref "JP2") (pin "1") (pinfunction "1_1") (pintype "passive"))
      (node (ref "JP2") (pin "2") (pinfunction "2_2") (pintype "passive"))
      (node (ref "JP3") (pin "3") (pinfunction "3_3") (pintype "passive"))
      (node (ref "L1") (pin "1") (pinfunction "1_1") (pintype "passive"))
      (node (ref "L5") (pin "1") (pinfunction "1_1") (pintype "passive"))
      (node (ref "PS1") (pin "10") (pinfunction "GND_2_10") (pintype "bidirectional"))
      (node (ref "Q1") (pin "3") (pinfunction "N1S/N2S_3") (pintype "bidirectional"))
      (node (ref "Q10") (pin "2") (pinfunction "S_2") (pintype "input"))
      (node (ref "Q11") (pin "2") (pinfunction "S_2") (pintype "input"))
      (node (ref "Q12") (pin "2") (pinfunction "S_2") (pintype "input"))
      (node (ref "Q13") (pin "2") (pinfunction "S_2") (pintype "input"))
      (node (ref "Q14") (pin "2") (pinfunction "S_2") (pintype "input"))
      (node (ref "Q15") (pin "2") (pinfunction "S_2") (pintype "input"))
      (node (ref "Q18") (pin "2") (pinfunction "S_2") (pintype "input"))
      (node (ref "Q19") (pin "2") (pinfunction "S_2") (pintype "input"))
      (node (ref "Q2") (pin "3") (pinfunction "N1S/N2S_3") (pintype "bidirectional"))
      (node (ref "Q20") (pin "2") (pinfunction "S_2") (pintype "input"))
      (node (ref "Q21") (pin "2") (pinfunction "S_2") (pintype "input"))
      (node (ref "R_2V1") (pin "2") (pinfunction "2_2") (pintype "passive"))
      (node (ref "R_FBB2") (pin "1") (pinfunction "1_1") (pintype "passive"))
      (node (ref "R_LED1_PULLUP") (pin "1") (pinfunction "1_1") (pintype "passive"))
      (node (ref "R_LED1_PULLUP1") (pin "1") (pinfunction "1_1") (pintype "passive"))
      (node (ref "R_LED1_PULLUP2") (pin "1") (pinfunction "1_1") (pintype "passive"))
      (node (ref "R_LED1_PULLUP3") (pin "1") (pinfunction "1_1") (pintype "passive"))
      (node (ref "R_LED6") (pin "2") (pinfunction "2_2") (pintype "passive"))
      (node (ref "R_PWR1") (pin "1") (pinfunction "1_1") (pintype "passive"))
      (node (ref "R_R11") (pin "1") (pinfunction "1_1") (pintype "passive"))
      (node (ref "R_R13") (pin "1") (pinfunction "1_1") (pintype "passive"))
      (node (ref "R_R15") (pin "1") (pinfunction "1_1") (pintype "passive"))
      (node (ref "R_R16") (pin "1") (pinfunction "1_1") (pintype "passive"))
      (node (ref "R_R18") (pin "1") (pinfunction "1_1") (pintype "passive"))
      (node (ref "R_R9") (pin "1") (pinfunction "1_1") (pintype "passive"))
      (node (ref "R_VM2") (pin "1") (pinfunction "1_1") (pintype "passive"))
      (node (ref "S1") (pin "5") (pinfunction "GND_5") (pintype "bidirectional"))
      (node (ref "S3") (pin "4") (pinfunction "NO_2_4") (pintype "bidirectional"))
      (node (ref "S3") (pin "5") (pinfunction "GND_5") (pintype "bidirectional"))
    )
    (net (code "19") (name "INT") (class "Default")
      (node (ref "IC7") (pin "12") (pinfunction "INT_12") (pintype "bidirectional"))
      (node (ref "IC9") (pin "29") (pinfunction "PB10_29") (pintype "bidirectional"))
    )
    (net (code "20") (name "JTCK") (class "Default")
      (node (ref "IC9") (pin "49") (pinfunction "PA14_49") (pintype "bidirectional"))
      (node (ref "J4") (pin "6") (pinfunction "6_6") (pintype "passive"))
    )
    (net (code "21") (name "JTMS") (class "Default")
      (node (ref "IC9") (pin "46") (pinfunction "PA13_46") (pintype "bidirectional"))
      (node (ref "J4") (pin "8") (pinfunction "8_8") (pintype "passive"))
    )
    (net (code "22") (name "LED1") (class "Default")
      (node (ref "IC9") (pin "4") (pinfunction "PC15_4") (pintype "bidirectional"))
      (node (ref "Q18") (pin "1") (pinfunction "G_1") (pintype "input"))
      (node (ref "R_LED1_PULLUP") (pin "2") (pinfunction "2_2") (pintype "passive"))
    )
    (net (code "23") (name "LED2") (class "Default")
      (node (ref "IC9") (pin "6") (pinfunction "PH1_6") (pintype "bidirectional"))
      (node (ref "Q19") (pin "1") (pinfunction "G_1") (pintype "input"))
      (node (ref "R_LED1_PULLUP1") (pin "2") (pinfunction "2_2") (pintype "passive"))
    )
    (net (code "24") (name "LED3") (class "Default")
      (node (ref "IC9") (pin "44") (pinfunction "PA11_44") (pintype "bidirectional"))
      (node (ref "Q20") (pin "1") (pinfunction "G_1") (pintype "input"))
      (node (ref "R_LED1_PULLUP2") (pin "2") (pinfunction "2_2") (pintype "passive"))
    )
    (net (code "25") (name "LED4") (class "Default")
      (node (ref "IC9") (pin "45") (pinfunction "PA12_45") (pintype "bidirectional"))
      (node (ref "Q21") (pin "1") (pinfunction "G_1") (pintype "input"))
      (node (ref "R_LED1_PULLUP3") (pin "2") (pinfunction "2_2") (pintype "passive"))
    )
    (net (code "26") (name "LED7") (class "Default")
      (node (ref "IC9") (pin "30") (pinfunction "PB11_30") (pintype "bidirectional"))
      (node (ref "R_LED8") (pin "1") (pinfunction "1_1") (pintype "passive"))
    )
    (net (code "27") (name "LED8") (class "Default")
      (node (ref "IC9") (pin "33") (pinfunction "PB12_33") (pintype "bidirectional"))
      (node (ref "R_LED9") (pin "2") (pinfunction "2_2") (pintype "passive"))
    )
    (net (code "28") (name "LENCHA") (class "Default")
      (node (ref "IC9") (pin "14") (pinfunction "PA0_WKUP_14") (pintype "bidirectional"))
      (node (ref "J2") (pin "6") (pinfunction "6_6") (pintype "passive"))
    )
    (net (code "29") (name "LENCHB") (class "Default")
      (node (ref "IC9") (pin "15") (pinfunction "PA1_15") (pintype "bidirectional"))
      (node (ref "J2") (pin "5") (pinfunction "5_5") (pintype "passive"))
    )
    (net (code "30") (name "LF_EMITTER") (class "Default")
      (node (ref "IC9") (pin "5") (pinfunction "PH0_5") (pintype "bidirectional"))
      (node (ref "Q10") (pin "1") (pinfunction "G_1") (pintype "input"))
      (node (ref "R_R9") (pin "2") (pinfunction "2_2") (pintype "passive"))
    )
    (net (code "31") (name "LF_RECEIVER") (class "Default")
      (node (ref "IC9") (pin "10") (pinfunction "PC2_10") (pintype "bidirectional"))
      (node (ref "Q9") (pin "1") (pinfunction "E_1") (pintype "bidirectional"))
      (node (ref "R_R7") (pin "2") (pinfunction "2_2") (pintype "passive"))
    )
    (net (code "32") (name "LPWMA") (class "Default")
      (node (ref "IC5") (pin "2") (pinfunction "INA_2") (pintype "input"))
      (node (ref "IC9") (pin "62") (pinfunction "PB9_62") (pintype "bidirectional"))
      (node (ref "R_PWMUP_1") (pin "1") (pinfunction "1_1") (pintype "passive"))
    )
    (net (code "33") (name "LPWMB") (class "Default")
      (node (ref "IC5") (pin "4") (pinfunction "INB_4") (pintype "input"))
      (node (ref "IC9") (pin "61") (pinfunction "PB8_61") (pintype "bidirectional"))
      (node (ref "R_PWMUP_2") (pin "1") (pinfunction "1_1") (pintype "passive"))
    )
    (net (code "34") (name "L_EMITTER") (class "Default")
      (node (ref "IC9") (pin "2") (pinfunction "PC13_2") (pintype "bidirectional"))
      (node (ref "Q12") (pin "1") (pinfunction "G_1") (pintype "input"))
      (node (ref "R_R13") (pin "2") (pinfunction "2_2") (pintype "passive"))
    )
    (net (code "35") (name "L_RECEIVER_1") (class "Default")
      (node (ref "IC9") (pin "9") (pinfunction "PC1_9") (pintype "bidirectional"))
      (node (ref "Q8") (pin "1") (pinfunction "E_1") (pintype "bidirectional"))
      (node (ref "R_R6") (pin "2") (pinfunction "2_2") (pintype "passive"))
    )
    (net (code "36") (name "MID_RECEIVER") (class "Default")
      (node (ref "IC9") (pin "16") (pinfunction "PA2_16") (pintype "bidirectional"))
      (node (ref "Q3") (pin "1") (pinfunction "E_1") (pintype "bidirectional"))
      (node (ref "R_R1") (pin "2") (pinfunction "2_2") (pintype "passive"))
    )
    (net (code "37") (name "M_EMITTER") (class "Default")
      (node (ref "IC9") (pin "40") (pinfunction "PC9_40") (pintype "bidirectional"))
      (node (ref "Q14") (pin "1") (pinfunction "G_1") (pintype "input"))
      (node (ref "R_R16") (pin "2") (pinfunction "2_2") (pintype "passive"))
    )
    (net (code "38") (name "NCS") (class "Default")
      (node (ref "IC7") (pin "22") (pinfunction "NCS_22") (pintype "bidirectional"))
      (node (ref "IC9") (pin "17") (pinfunction "PA3_17") (pintype "bidirectional"))
    )
    (net (code "39") (name "Net-(C_A3.3V-Pad1)") (class "Default")
      (node (ref "C_A3.3V") (pin "1") (pinfunction "1_1") (pintype "passive"))
      (node (ref "L1") (pin "2") (pinfunction "2_2") (pintype "passive"))
    )
    (net (code "40") (name "Net-(C_G1-Pad1)") (class "Default")
      (node (ref "C_G1") (pin "1") (pinfunction "1_1") (pintype "passive"))
      (node (ref "C_G2") (pin "2") (pinfunction "2_2") (pintype "passive"))
    )
    (net (code "41") (name "Net-(C_G3-Pad2)") (class "Default")
      (node (ref "C_G3") (pin "2") (pinfunction "2_2") (pintype "passive"))
      (node (ref "C_G4") (pin "2") (pinfunction "2_2") (pintype "passive"))
    )
    (net (code "42") (name "Net-(D1-PadC)") (class "Default")
      (node (ref "D1") (pin "C") (pinfunction "C_C") (pintype "passive"))
      (node (ref "R_R8") (pin "2") (pinfunction "2_2") (pintype "passive"))
    )
    (net (code "43") (name "Net-(D2-PadC)") (class "Default")
      (node (ref "D2") (pin "C") (pinfunction "C_C") (pintype "passive"))
      (node (ref "R_R10") (pin "2") (pinfunction "2_2") (pintype "passive"))
    )
    (net (code "44") (name "Net-(D3-PadC)") (class "Default")
      (node (ref "D3") (pin "C") (pinfunction "C_C") (pintype "passive"))
      (node (ref "R_R12") (pin "2") (pinfunction "2_2") (pintype "passive"))
    )
    (net (code "45") (name "Net-(D4-PadC)") (class "Default")
      (node (ref "D4") (pin "C") (pinfunction "C_C") (pintype "passive"))
      (node (ref "R_R14") (pin "2") (pinfunction "2_2") (pintype "passive"))
    )
    (net (code "46") (name "Net-(D5-PadC)") (class "Default")
      (node (ref "D5") (pin "C") (pinfunction "C_C") (pintype "passive"))
      (node (ref "R_R17") (pin "2") (pinfunction "2_2") (pintype "passive"))
    )
    (net (code "47") (name "Net-(D7-A)") (class "Default")
      (node (ref "D7") (pin "2") (pinfunction "A_2") (pintype "bidirectional"))
      (node (ref "LS1") (pin "1") (pinfunction "+_1") (pintype "bidirectional"))
      (node (ref "Q15") (pin "3") (pinfunction "D_3") (pintype "input"))
    )
    (net (code "48") (name "Net-(D7-K)") (class "Default")
      (node (ref "C_EM11") (pin "1") (pinfunction "1_1") (pintype "passive"))
      (node (ref "C_EM12") (pin "2") (pinfunction "2_2") (pintype "passive"))
      (node (ref "D7") (pin "1") (pinfunction "K_1") (pintype "bidirectional"))
      (node (ref "L7") (pin "1") (pinfunction "1_1") (pintype "passive"))
      (node (ref "LS1") (pin "2") (pinfunction "-_2") (pintype "bidirectional"))
    )
    (net (code "49") (name "Net-(D11-PadC)") (class "Default")
      (node (ref "D11") (pin "C") (pinfunction "C_C") (pintype "passive"))
      (node (ref "R_LED1") (pin "2") (pinfunction "2_2") (pintype "passive"))
    )
    (net (code "50") (name "Net-(D14-PadC)") (class "Default")
      (node (ref "D14") (pin "C") (pinfunction "C_C") (pintype "passive"))
      (node (ref "R_LED2") (pin "2") (pinfunction "2_2") (pintype "passive"))
    )
    (net (code "51") (name "Net-(D17-PadC)") (class "Default")
      (node (ref "D17") (pin "C") (pinfunction "C_C") (pintype "passive"))
      (node (ref "R_LED3") (pin "2") (pinfunction "2_2") (pintype "passive"))
    )
    (net (code "52") (name "Net-(D20-PadC)") (class "Default")
      (node (ref "D20") (pin "C") (pinfunction "C_C") (pintype "passive"))
      (node (ref "R_LED4") (pin "2") (pinfunction "2_2") (pintype "passive"))
    )
    (net (code "53") (name "Net-(D22-PadA)") (class "Default")
      (node (ref "D22") (pin "A") (pinfunction "A_A") (pintype "passive"))
      (node (ref "R_LED9") (pin "1") (pinfunction "1_1") (pintype "passive"))
    )
    (net (code "54") (name "Net-(D23-PadA)") (class "Default")
      (node (ref "D23") (pin "A") (pinfunction "A_A") (pintype "passive"))
      (node (ref "R_LED8") (pin "2") (pinfunction "2_2") (pintype "passive"))
    )
    (net (code "55") (name "Net-(IC1-FB)") (class "Default")
      (node (ref "IC1") (pin "2") (pinfunction "FB_2") (pintype "bidirectional"))
      (node (ref "R_FBB2") (pin "2") (pinfunction "2_2") (pintype "passive"))
      (node (ref "R_FBT1") (pin "1") (pinfunction "1_1") (pintype "passive"))
    )
    (net (code "56") (name "Net-(IC1-PG)") (class "Default")
      (node (ref "IC1") (pin "3") (pinfunction "PG_3") (pintype "bidirectional"))
      (node (ref "R_PG1") (pin "2") (pinfunction "2_2") (pintype "passive"))
    )
    (net (code "57") (name "Net-(IC1-SS)") (class "Default")
      (node (ref "C_SS1") (pin "2") (pinfunction "2_2") (pintype "passive"))
      (node (ref "IC1") (pin "1") (pinfunction "SS_1") (pintype "bidirectional"))
    )
    (net (code "58") (name "Net-(IC2-EN)") (class "Default")
      (node (ref "C_3.3V_5") (pin "2") (pinfunction "2_2") (pintype "passive"))
      (node (ref "C_A3.3V_1") (pin "2") (pinfunction "2_2") (pintype "passive"))
      (node (ref "IC2") (pin "1") (pinfunction "IN_1") (pintype "bidirectional"))
      (node (ref "IC2") (pin "3") (pinfunction "EN_3") (pintype "bidirectional"))
      (node (ref "L2") (pin "2") (pinfunction "2_2") (pintype "passive"))
    )
    (net (code "59") (name "Net-(IC2-NR{slash}FB)") (class "Default")
      (node (ref "CNR") (pin "2") (pinfunction "2_2") (pintype "passive"))
      (node (ref "IC2") (pin "4") (pinfunction "NR/FB_4") (pintype "bidirectional"))
    )
    (net (code "60") (name "Net-(IC4-VIN)") (class "Default")
      (node (ref "C5V_1") (pin "2") (pinfunction "2_2") (pintype "passive"))
      (node (ref "C5V_4") (pin "2") (pinfunction "2_2") (pintype "passive"))
      (node (ref "IC4") (pin "3") (pinfunction "VIN_3") (pintype "bidirectional"))
      (node (ref "L4") (pin "2") (pinfunction "2_2") (pintype "passive"))
    )
    (net (code "61") (name "Net-(IC5-OUTA)") (class "Default")
      (node (ref "IC5") (pin "7") (pinfunction "OUTA_7") (pintype "bidirectional"))
      (node (ref "Q1") (pin "1") (pinfunction "N1G_1") (pintype "bidirectional"))
      (node (ref "Q1") (pin "8") (pinfunction "P1G_8") (pintype "bidirectional"))
    )
    (net (code "62") (name "Net-(IC5-OUTB)") (class "Default")
      (node (ref "IC5") (pin "5") (pinfunction "OUTB_5") (pintype "bidirectional"))
      (node (ref "Q1") (pin "4") (pinfunction "N2G_4") (pintype "bidirectional"))
      (node (ref "Q1") (pin "5") (pinfunction "P2G_5") (pintype "bidirectional"))
    )
    (net (code "63") (name "Net-(IC6-OUTA)") (class "Default")
      (node (ref "IC6") (pin "7") (pinfunction "OUTA_7") (pintype "bidirectional"))
      (node (ref "Q2") (pin "1") (pinfunction "N1G_1") (pintype "bidirectional"))
      (node (ref "Q2") (pin "8") (pinfunction "P1G_8") (pintype "bidirectional"))
    )
    (net (code "64") (name "Net-(IC6-OUTB)") (class "Default")
      (node (ref "IC6") (pin "5") (pinfunction "OUTB_5") (pintype "bidirectional"))
      (node (ref "Q2") (pin "4") (pinfunction "N2G_4") (pintype "bidirectional"))
      (node (ref "Q2") (pin "5") (pinfunction "P2G_5") (pintype "bidirectional"))
    )
    (net (code "65") (name "Net-(IC7-GND_1)") (class "Default")
      (node (ref "IC7") (pin "18") (pinfunction "GND_1_18") (pintype "bidirectional"))
      (node (ref "IC7") (pin "20") (pinfunction "RESV_2_20") (pintype "bidirectional"))
      (node (ref "IC7") (pin "25") (pinfunction "GND_2_25") (pintype "bidirectional"))
    )
    (net (code "66") (name "Net-(IC7-REGOUT)") (class "Default")
      (node (ref "C_G2") (pin "1") (pinfunction "1_1") (pintype "passive"))
      (node (ref "IC7") (pin "10") (pinfunction "REGOUT_10") (pintype "bidirectional"))
    )
    (net (code "67") (name "Net-(IC9-VCAP_1)") (class "Default")
      (node (ref "C_VCAP1") (pin "2") (pinfunction "2_2") (pintype "passive"))
      (node (ref "IC9") (pin "31") (pinfunction "VCAP_1_31") (pintype "bidirectional"))
    )
    (net (code "68") (name "Net-(IC9-VCAP_2)") (class "Default")
      (node (ref "C_VCAP2") (pin "1") (pinfunction "1_1") (pintype "passive"))
      (node (ref "IC9") (pin "47") (pinfunction "VCAP_2_47") (pintype "bidirectional"))
    )
    (net (code "69") (name "Net-(PS1-FB)") (class "Default")
      (node (ref "C2V_2") (pin "2") (pinfunction "2_2") (pintype "passive"))
      (node (ref "PS1") (pin "8") (pinfunction "FB_8") (pintype "bidirectional"))
      (node (ref "R_2V1") (pin "1") (pinfunction "1_1") (pintype "passive"))
      (node (ref "R_2V2") (pin "1") (pinfunction "1_1") (pintype "passive"))
    )
    (net (code "70") (name "Net-(PS1-PG)") (class "Default")
      (node (ref "PS1") (pin "4") (pinfunction "PG_4") (pintype "bidirectional"))
      (node (ref "R_2V3") (pin "2") (pinfunction "2_2") (pintype "passive"))
    )
    (net (code "71") (name "Net-(PWR_LED1-PadC)") (class "Default")
      (node (ref "PWR_LED1") (pin "C") (pinfunction "C_C") (pintype "passive"))
      (node (ref "R_PWR1") (pin "2") (pinfunction "2_2") (pintype "passive"))
    )
    (net (code "72") (name "Net-(Q1-N1D{slash}P1D)") (class "Default")
      (node (ref "J2") (pin "2") (pinfunction "2_2") (pintype "passive"))
      (node (ref "Q1") (pin "2") (pinfunction "N1D/P1D_2") (pintype "bidirectional"))
    )
    (net (code "73") (name "Net-(Q1-N2D{slash}P2D)") (class "Default")
      (node (ref "J2") (pin "1") (pinfunction "1_1") (pintype "passive"))
      (node (ref "Q1") (pin "6") (pinfunction "N2D/P2D_6") (pintype "bidirectional"))
    )
    (net (code "74") (name "Net-(Q2-N1D{slash}P1D)") (class "Default")
      (node (ref "J3") (pin "2") (pinfunction "2_2") (pintype "passive"))
      (node (ref "Q2") (pin "2") (pinfunction "N1D/P1D_2") (pintype "bidirectional"))
    )
    (net (code "75") (name "Net-(Q2-N2D{slash}P2D)") (class "Default")
      (node (ref "J3") (pin "1") (pinfunction "1_1") (pintype "passive"))
      (node (ref "Q2") (pin "6") (pinfunction "N2D/P2D_6") (pintype "bidirectional"))
    )
    (net (code "76") (name "Net-(Q10-D)") (class "Default")
      (node (ref "Q10") (pin "3") (pinfunction "D_3") (pintype "input"))
      (node (ref "R_R8") (pin "1") (pinfunction "1_1") (pintype "passive"))
    )
    (net (code "77") (name "Net-(Q11-D)") (class "Default")
      (node (ref "Q11") (pin "3") (pinfunction "D_3") (pintype "input"))
      (node (ref "R_R10") (pin "1") (pinfunction "1_1") (pintype "passive"))
    )
    (net (code "78") (name "Net-(Q12-D)") (class "Default")
      (node (ref "Q12") (pin "3") (pinfunction "D_3") (pintype "input"))
      (node (ref "R_R12") (pin "1") (pinfunction "1_1") (pintype "passive"))
    )
    (net (code "79") (name "Net-(Q13-D)") (class "Default")
      (node (ref "Q13") (pin "3") (pinfunction "D_3") (pintype "input"))
      (node (ref "R_R14") (pin "1") (pinfunction "1_1") (pintype "passive"))
    )
    (net (code "80") (name "Net-(Q14-D)") (class "Default")
      (node (ref "Q14") (pin "3") (pinfunction "D_3") (pintype "input"))
      (node (ref "R_R17") (pin "1") (pinfunction "1_1") (pintype "passive"))
    )
    (net (code "81") (name "Net-(Q18-D)") (class "Default")
      (node (ref "Q18") (pin "3") (pinfunction "D_3") (pintype "input"))
      (node (ref "R_LED1") (pin "1") (pinfunction "1_1") (pintype "passive"))
    )
    (net (code "82") (name "Net-(Q19-D)") (class "Default")
      (node (ref "Q19") (pin "3") (pinfunction "D_3") (pintype "input"))
      (node (ref "R_LED2") (pin "1") (pinfunction "1_1") (pintype "passive"))
    )
    (net (code "83") (name "Net-(Q20-D)") (class "Default")
      (node (ref "Q20") (pin "3") (pinfunction "D_3") (pintype "input"))
      (node (ref "R_LED3") (pin "1") (pinfunction "1_1") (pintype "passive"))
    )
    (net (code "84") (name "Net-(Q21-D)") (class "Default")
      (node (ref "Q21") (pin "3") (pinfunction "D_3") (pintype "input"))
      (node (ref "R_LED4") (pin "1") (pinfunction "1_1") (pintype "passive"))
    )
    (net (code "85") (name "Net-(S2-O)") (class "Default")
      (node (ref "J1") (pin "1") (pinfunction "1_1") (pintype "bidirectional"))
      (node (ref "S2") (pin "1") (pinfunction "O_1") (pintype "passive"))
      (node (ref "S2") (pin "2") (pinfunction "P_2") (pintype "passive"))
    )
    (net (code "86") (name "RENCHA") (class "Default")
      (node (ref "IC9") (pin "50") (pinfunction "PA15_50") (pintype "bidirectional"))
      (node (ref "J3") (pin "6") (pinfunction "6_6") (pintype "passive"))
    )
    (net (code "87") (name "RENCHB") (class "Default")
      (node (ref "IC9") (pin "55") (pinfunction "PB3_55") (pintype "bidirectional"))
      (node (ref "J3") (pin "5") (pinfunction "5_5") (pintype "passive"))
    )
    (net (code "88") (name "RESET") (class "Default")
      (node (ref "C_RST") (pin "1") (pinfunction "1_1") (pintype "passive"))
      (node (ref "DS1") (pin "12") (pinfunction "~{RESET}_12") (pintype "bidirectional"))
      (node (ref "IC9") (pin "7") (pinfunction "NRST_7") (pintype "input"))
      (node (ref "R_LED7") (pin "2") (pinfunction "2_2") (pintype "passive"))
      (node (ref "S3") (pin "1") (pinfunction "COM_1_1") (pintype "bidirectional"))
    )
    (net (code "89") (name "RF_EMITTER") (class "Default")
      (node (ref "IC9") (pin "41") (pinfunction "PA8_41") (pintype "bidirectional"))
      (node (ref "Q13") (pin "1") (pinfunction "G_1") (pintype "input"))
      (node (ref "R_R15") (pin "2") (pinfunction "2_2") (pintype "passive"))
    )
    (net (code "90") (name "RF_RECEIVER") (class "Default")
      (node (ref "IC9") (pin "26") (pinfunction "PB0_26") (pintype "bidirectional"))
      (node (ref "Q4") (pin "1") (pinfunction "E_1") (pintype "bidirectional"))
      (node (ref "R_R2") (pin "2") (pinfunction "2_2") (pintype "passive"))
    )
    (net (code "91") (name "RPWMA") (class "Default")
      (node (ref "IC6") (pin "2") (pinfunction "INA_2") (pintype "input"))
      (node (ref "IC9") (pin "59") (pinfunction "PB7_59") (pintype "bidirectional"))
      (node (ref "R_PWMUP3") (pin "1") (pinfunction "1_1") (pintype "passive"))
    )
    (net (code "92") (name "RPWMB") (class "Default")
      (node (ref "IC6") (pin "4") (pinfunction "INB_4") (pintype "input"))
      (node (ref "IC9") (pin "58") (pinfunction "PB6_58") (pintype "bidirectional"))
      (node (ref "R_PWMUP4") (pin "1") (pinfunction "1_1") (pintype "passive"))
    )
    (net (code "93") (name "RS") (class "Default")
      (node (ref "DS1") (pin "5") (pinfunction "RS_5") (pintype "bidirectional"))
      (node (ref "IC9") (pin "38") (pinfunction "PC7_38") (pintype "bidirectional"))
    )
    (net (code "94") (name "RX") (class "Default")
      (node (ref "IC9") (pin "43") (pinfunction "PA10_43") (pintype "bidirectional"))
      (node (ref "J4") (pin "5") (pinfunction "5_5") (pintype "passive"))
    )
    (net (code "95") (name "R_EMITTER") (class "Default")
      (node (ref "IC9") (pin "39") (pinfunction "PC8_39") (pintype "bidirectional"))
      (node (ref "Q11") (pin "1") (pinfunction "G_1") (pintype "input"))
      (node (ref "R_R11") (pin "2") (pinfunction "2_2") (pintype "passive"))
    )
    (net (code "96") (name "R_RECEIVER_1") (class "Default")
      (node (ref "IC9") (pin "24") (pinfunction "PC4_24") (pintype "bidirectional"))
      (node (ref "Q6") (pin "1") (pinfunction "E_1") (pintype "bidirectional"))
      (node (ref "R_R4") (pin "2") (pinfunction "2_2") (pintype "passive"))
    )
    (net (code "97") (name "SCLK") (class "Default")
      (node (ref "IC7") (pin "23") (pinfunction "SCL_/_SCLK_23") (pintype "bidirectional"))
      (node (ref "IC9") (pin "21") (pinfunction "PA5_21") (pintype "bidirectional"))
    )
    (net (code "98") (name "SDI") (class "Default")
      (node (ref "IC7") (pin "24") (pinfunction "SDA_/_SDI_24") (pintype "bidirectional"))
      (node (ref "IC9") (pin "23") (pinfunction "PA7_23") (pintype "bidirectional"))
    )
    (net (code "99") (name "SDO") (class "Default")
      (node (ref "IC7") (pin "9") (pinfunction "SDO_/_AD0_9") (pintype "bidirectional"))
      (node (ref "IC9") (pin "22") (pinfunction "PA6_22") (pintype "bidirectional"))
    )
    (net (code "100") (name "TX") (class "Default")
      (node (ref "IC9") (pin "42") (pinfunction "PA9_42") (pintype "bidirectional"))
      (node (ref "J4") (pin "7") (pinfunction "7_7") (pintype "passive"))
    )
    (net (code "101") (name "VOL_METER") (class "Default")
      (node (ref "IC9") (pin "27") (pinfunction "PB1_27") (pintype "bidirectional"))
      (node (ref "R_VM1") (pin "1") (pinfunction "1_1") (pintype "passive"))
      (node (ref "R_VM2") (pin "2") (pinfunction "2_2") (pintype "passive"))
    )
    (net (code "102") (name "VOL_METER_BOOST") (class "Default")
      (node (ref "IC9") (pin "11") (pinfunction "PC3_11") (pintype "bidirectional"))
    )
    (net (code "103") (name "V_BAT") (class "Default")
      (node (ref "C_VBAT2") (pin "1") (pinfunction "1_1") (pintype "passive"))
      (node (ref "S2") (pin "3") (pinfunction "S_3") (pintype "passive"))
      (node (ref "XFL4020") (pin "2") (pinfunction "2_2") (pintype "passive"))
    )
    (net (code "104") (name "V_BAT_FILTER") (class "Default")
      (node (ref "C_VBAT1") (pin "1") (pinfunction "1_1") (pintype "passive"))
      (node (ref "C_VBAT3") (pin "2") (pinfunction "2_2") (pintype "passive"))
      (node (ref "C_VBAT4") (pin "2") (pinfunction "2_2") (pintype "passive"))
      (node (ref "IC1") (pin "7") (pinfunction "EN_7") (pintype "bidirectional"))
      (node (ref "IC1") (pin "8") (pinfunction "VIN_8") (pintype "input"))
      (node (ref "R_VM1") (pin "2") (pinfunction "2_2") (pintype "passive"))
      (node (ref "XFL4020") (pin "1") (pinfunction "1_1") (pintype "passive"))
    )
    (net (code "105") (name "V_BOOST") (class "Default")
      (node (ref "C_M1") (pin "1") (pinfunction "1_1") (pintype "passive"))
      (node (ref "C_M2") (pin "2") (pinfunction "2_2") (pintype "passive"))
      (node (ref "C_M4") (pin "2") (pinfunction "2_2") (pintype "passive"))
      (node (ref "C_M5") (pin "1") (pinfunction "1_1") (pintype "passive"))
      (node (ref "C_MB_L") (pin "2") (pinfunction "2_2") (pintype "passive"))
      (node (ref "C_MB_R") (pin "2") (pinfunction "2_2") (pintype "passive"))
      (node (ref "IC5") (pin "6") (pinfunction "VDD_6") (pintype "power_in"))
      (node (ref "IC6") (pin "6") (pinfunction "VDD_6") (pintype "power_in"))
      (node (ref "Q1") (pin "7") (pinfunction "P1S/P2S_7") (pintype "bidirectional"))
      (node (ref "Q2") (pin "7") (pinfunction "P1S/P2S_7") (pintype "bidirectional"))
    )
    (net (code "106") (name "unconnected-(DS1-DATA_OUT-Pad1)") (class "Default")
      (node (ref "DS1") (pin "1") (pinfunction "DATA_OUT_1") (pintype "bidirectional"))
    )
    (net (code "107") (name "unconnected-(DS1-OSC-Pad2)") (class "Default")
      (node (ref "DS1") (pin "2") (pinfunction "OSC_2") (pintype "bidirectional"))
    )
    (net (code "108") (name "unconnected-(IC5-ENA-Pad1)") (class "Default")
      (node (ref "IC5") (pin "1") (pinfunction "ENA_1") (pintype "input"))
    )
    (net (code "109") (name "unconnected-(IC5-ENB-Pad8)") (class "Default")
      (node (ref "IC5") (pin "8") (pinfunction "ENB_8") (pintype "input"))
    )
    (net (code "110") (name "unconnected-(IC6-ENA-Pad1)") (class "Default")
      (node (ref "IC6") (pin "1") (pinfunction "ENA_1") (pintype "input"))
    )
    (net (code "111") (name "unconnected-(IC6-ENB-Pad8)") (class "Default")
      (node (ref "IC6") (pin "8") (pinfunction "ENB_8") (pintype "input"))
    )
    (net (code "112") (name "unconnected-(IC7-AUX_CL-Pad7)") (class "Default")
      (node (ref "IC7") (pin "7") (pinfunction "AUX_CL_7") (pintype "bidirectional"))
    )
    (net (code "113") (name "unconnected-(IC7-AUX_DA-Pad21)") (class "Default")
      (node (ref "IC7") (pin "21") (pinfunction "AUX_DA_21") (pintype "bidirectional"))
    )
    (net (code "114") (name "unconnected-(IC7-NC_1-Pad1)") (class "Default")
      (node (ref "IC7") (pin "1") (pinfunction "NC_1_1") (pintype "bidirectional"))
    )
    (net (code "115") (name "unconnected-(IC7-NC_2-Pad2)") (class "Default")
      (node (ref "IC7") (pin "2") (pinfunction "NC_2_2") (pintype "bidirectional"))
    )
    (net (code "116") (name "unconnected-(IC7-NC_3-Pad3)") (class "Default")
      (node (ref "IC7") (pin "3") (pinfunction "NC_3_3") (pintype "bidirectional"))
    )
    (net (code "117") (name "unconnected-(IC7-NC_4-Pad4)") (class "Default")
      (node (ref "IC7") (pin "4") (pinfunction "NC_4_4") (pintype "bidirectional"))
    )
    (net (code "118") (name "unconnected-(IC7-NC_5-Pad5)") (class "Default")
      (node (ref "IC7") (pin "5") (pinfunction "NC_5_5") (pintype "bidirectional"))
    )
    (net (code "119") (name "unconnected-(IC7-NC_6-Pad6)") (class "Default")
      (node (ref "IC7") (pin "6") (pinfunction "NC_6_6") (pintype "bidirectional"))
    )
    (net (code "120") (name "unconnected-(IC7-NC_7-Pad14)") (class "Default")
      (node (ref "IC7") (pin "14") (pinfunction "NC_7_14") (pintype "bidirectional"))
    )
    (net (code "121") (name "unconnected-(IC7-NC_8-Pad15)") (class "Default")
      (node (ref "IC7") (pin "15") (pinfunction "NC_8_15") (pintype "bidirectional"))
    )
    (net (code "122") (name "unconnected-(IC7-NC_9-Pad16)") (class "Default")
      (node (ref "IC7") (pin "16") (pinfunction "NC_9_16") (pintype "bidirectional"))
    )
    (net (code "123") (name "unconnected-(IC7-NC_10-Pad17)") (class "Default")
      (node (ref "IC7") (pin "17") (pinfunction "NC_10_17") (pintype "bidirectional"))
    )
    (net (code "124") (name "unconnected-(IC7-RESV_1-Pad19)") (class "Default")
      (node (ref "IC7") (pin "19") (pinfunction "RESV_1_19") (pintype "bidirectional"))
    )
    (net (code "125") (name "unconnected-(IC9-PB14-Pad35)") (class "Default")
      (node (ref "IC9") (pin "35") (pinfunction "PB14_35") (pintype "bidirectional"))
    )
    (net (code "126") (name "unconnected-(IC9-PC0-Pad8)") (class "Default")
      (node (ref "IC9") (pin "8") (pinfunction "PC0_8") (pintype "bidirectional"))
    )
    (net (code "127") (name "unconnected-(IC9-PC5-Pad25)") (class "Default")
      (node (ref "IC9") (pin "25") (pinfunction "PC5_25") (pintype "bidirectional"))
    )
    (net (code "128") (name "unconnected-(LS1-DUMMY-Pad3)") (class "Default")
      (node (ref "LS1") (pin "3") (pinfunction "DUMMY_3") (pintype "bidirectional"))
    )
    (net (code "129") (name "unconnected-(PS1-GND_1-Pad9)") (class "Default")
      (node (ref "PS1") (pin "9") (pinfunction "GND_1_9") (pintype "bidirectional"))
    )
    (net (code "130") (name "unconnected-(PS1-VIN_2-Pad2)") (class "Default")
      (node (ref "PS1") (pin "2") (pinfunction "VIN_2_2") (pintype "bidirectional"))
    )
    (net (code "131") (name "unconnected-(PS1-VOUT_2-Pad6)") (class "Default")
      (node (ref "PS1") (pin "6") (pinfunction "VOUT_2_6") (pintype "bidirectional"))
    )
    (net (code "132") (name "unconnected-(PS1-VOUT_3-Pad7)") (class "Default")
      (node (ref "PS1") (pin "7") (pinfunction "VOUT_3_7") (pintype "bidirectional"))
    )
    (net (code "133") (name "unconnected-(S1-COM_2-Pad3)") (class "Default")
      (node (ref "S1") (pin "3") (pinfunction "COM_2_3") (pintype "bidirectional"))
    )
    (net (code "134") (name "unconnected-(S1-NO_1-Pad2)") (class "Default")
      (node (ref "S1") (pin "2") (pinfunction "NO_1_2") (pintype "bidirectional"))
    )
    (net (code "135") (name "unconnected-(S3-COM_2-Pad3)") (class "Default")
      (node (ref "S3") (pin "3") (pinfunction "COM_2_3") (pintype "bidirectional"))
    )
    (net (code "136") (name "unconnected-(S3-NO_1-Pad2)") (class "Default")
      (node (ref "S3") (pin "2") (pinfunction "NO_1_2") (pintype "bidirectional"))
    )
  )
)
